# schematic.net
KiCad netlist of a schematic drawn in EAGLE
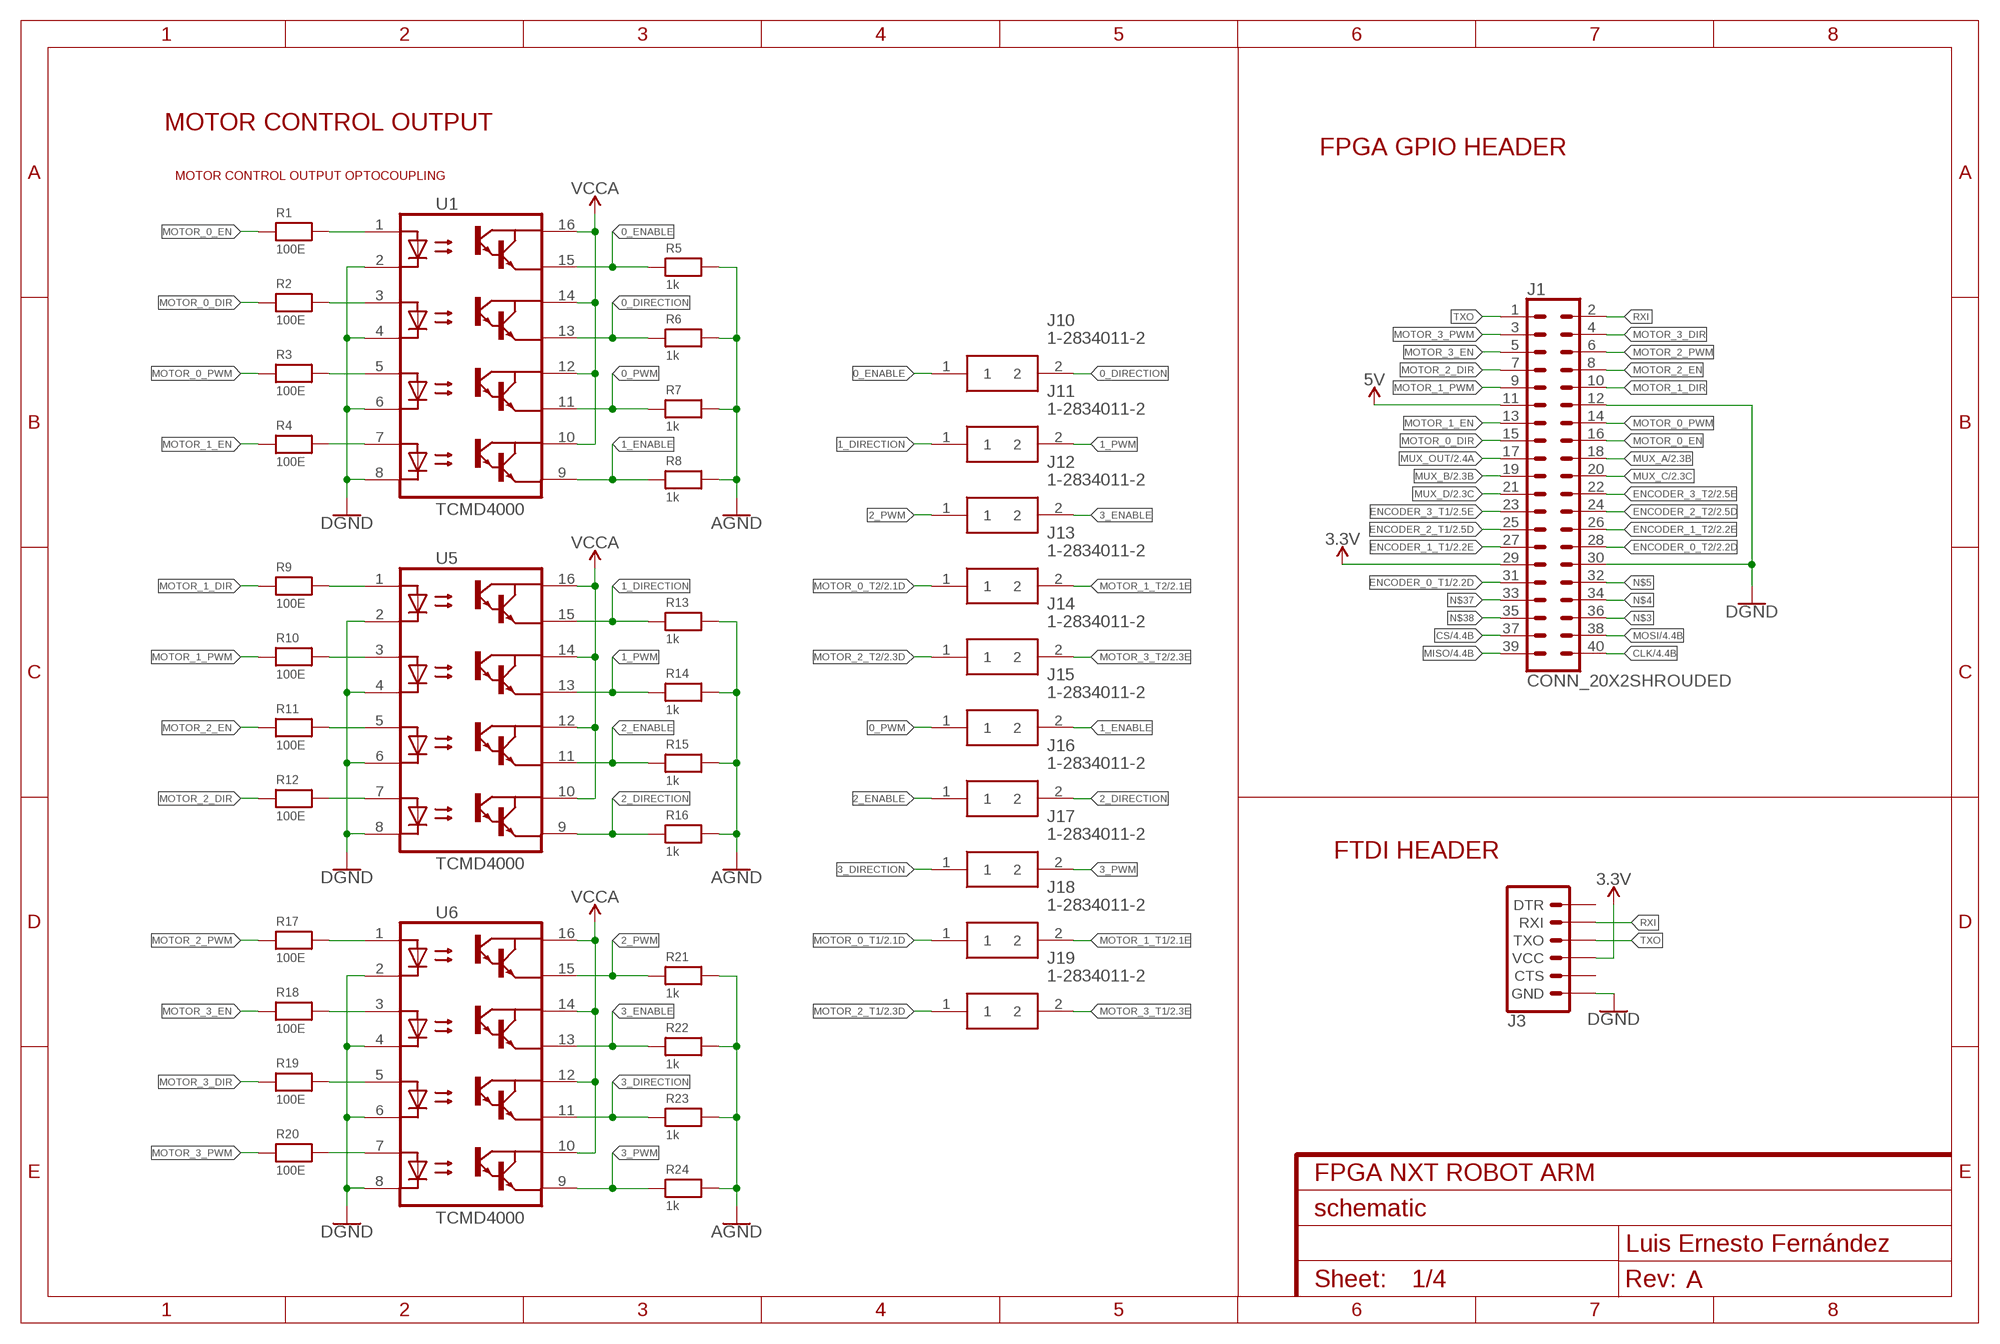
[diagram p0: schematic, sheet 1]
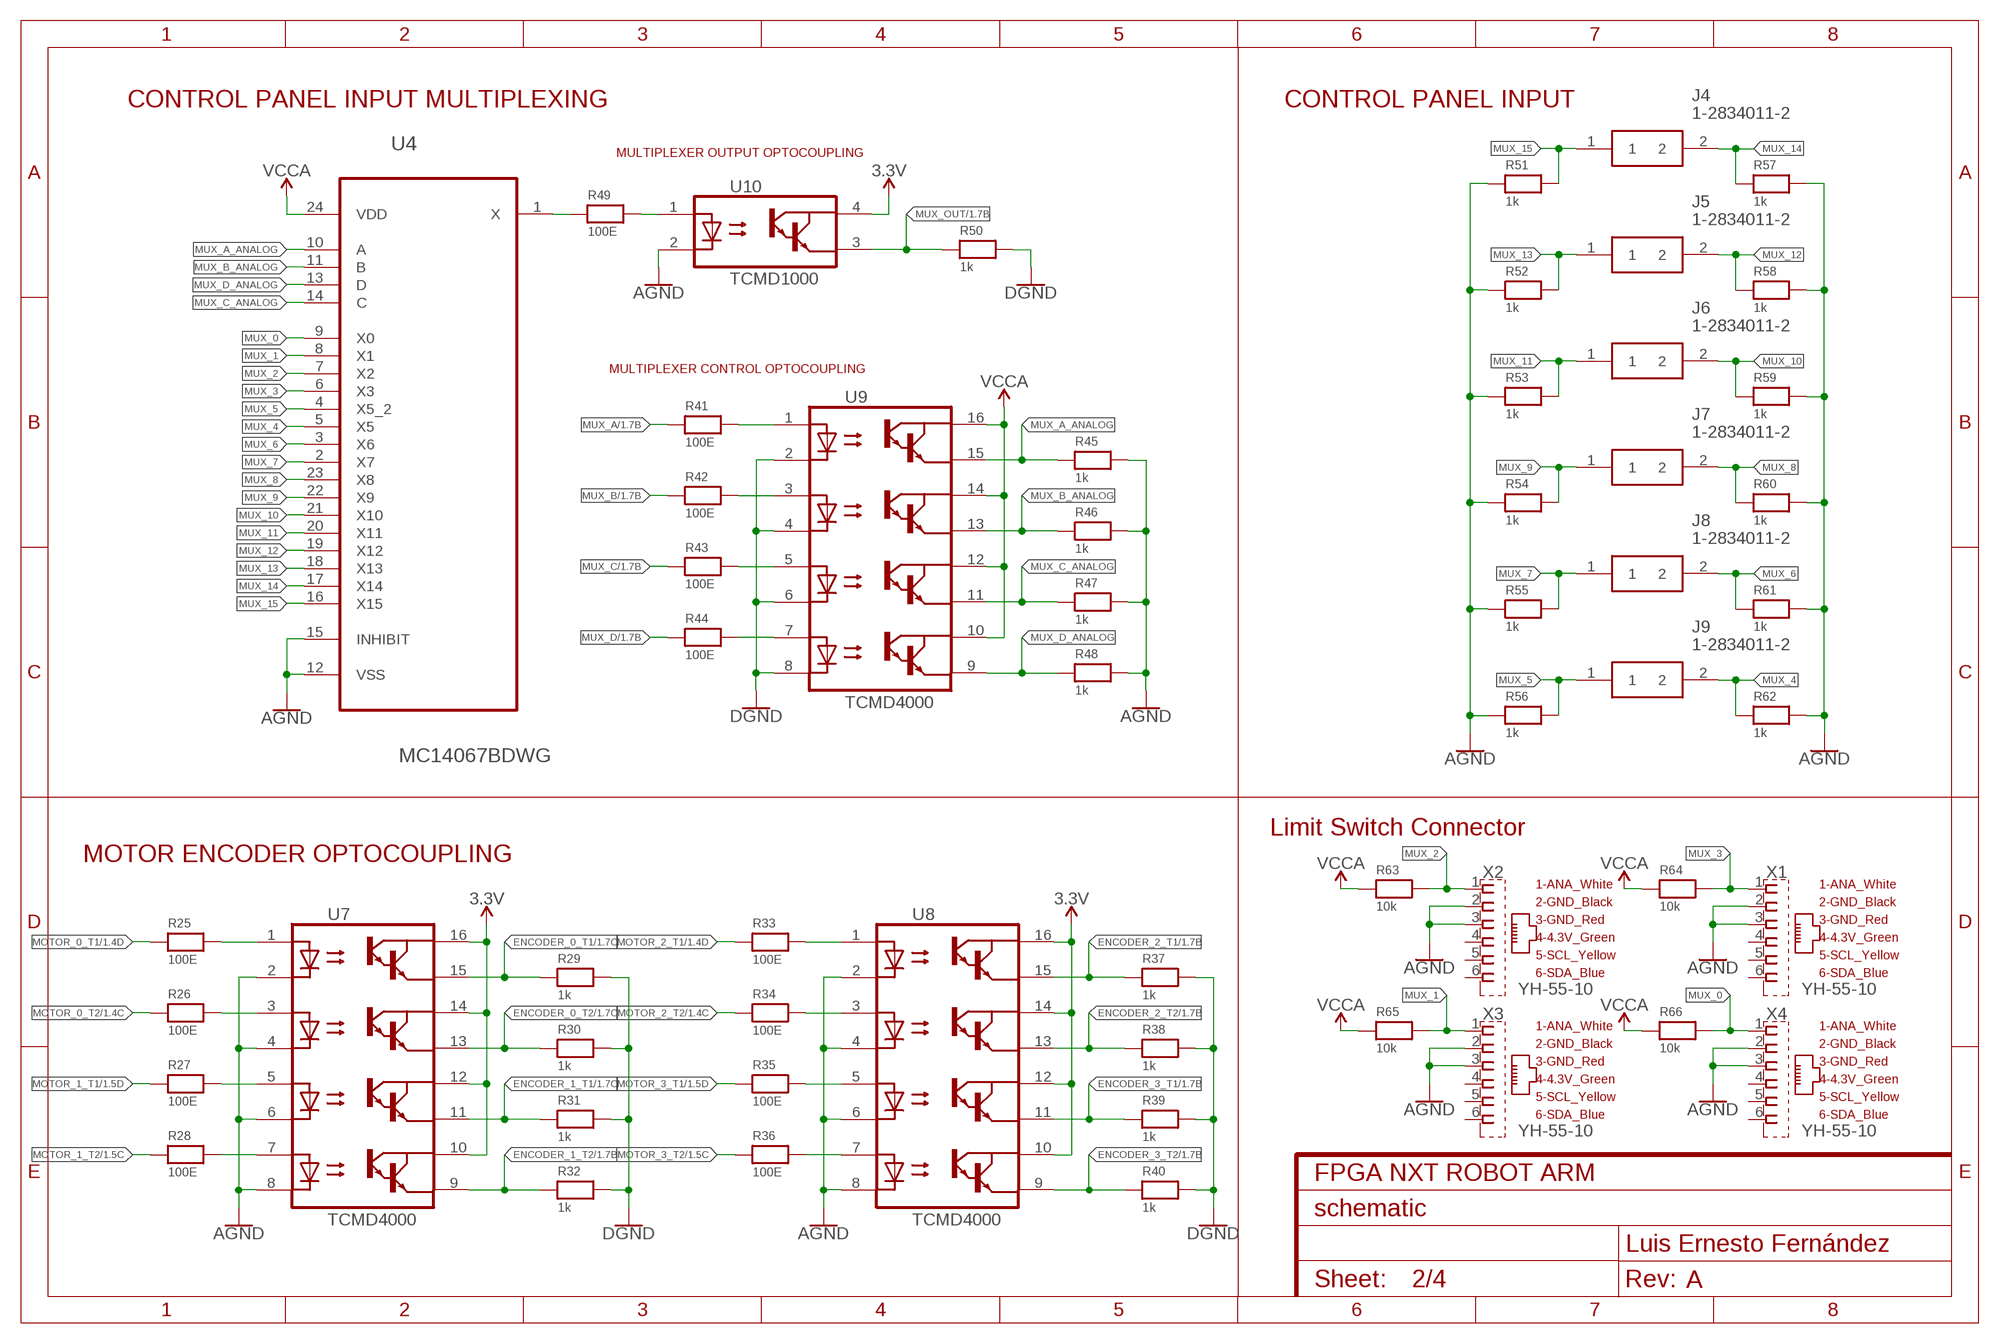
[diagram p1: schematic, sheet 2]
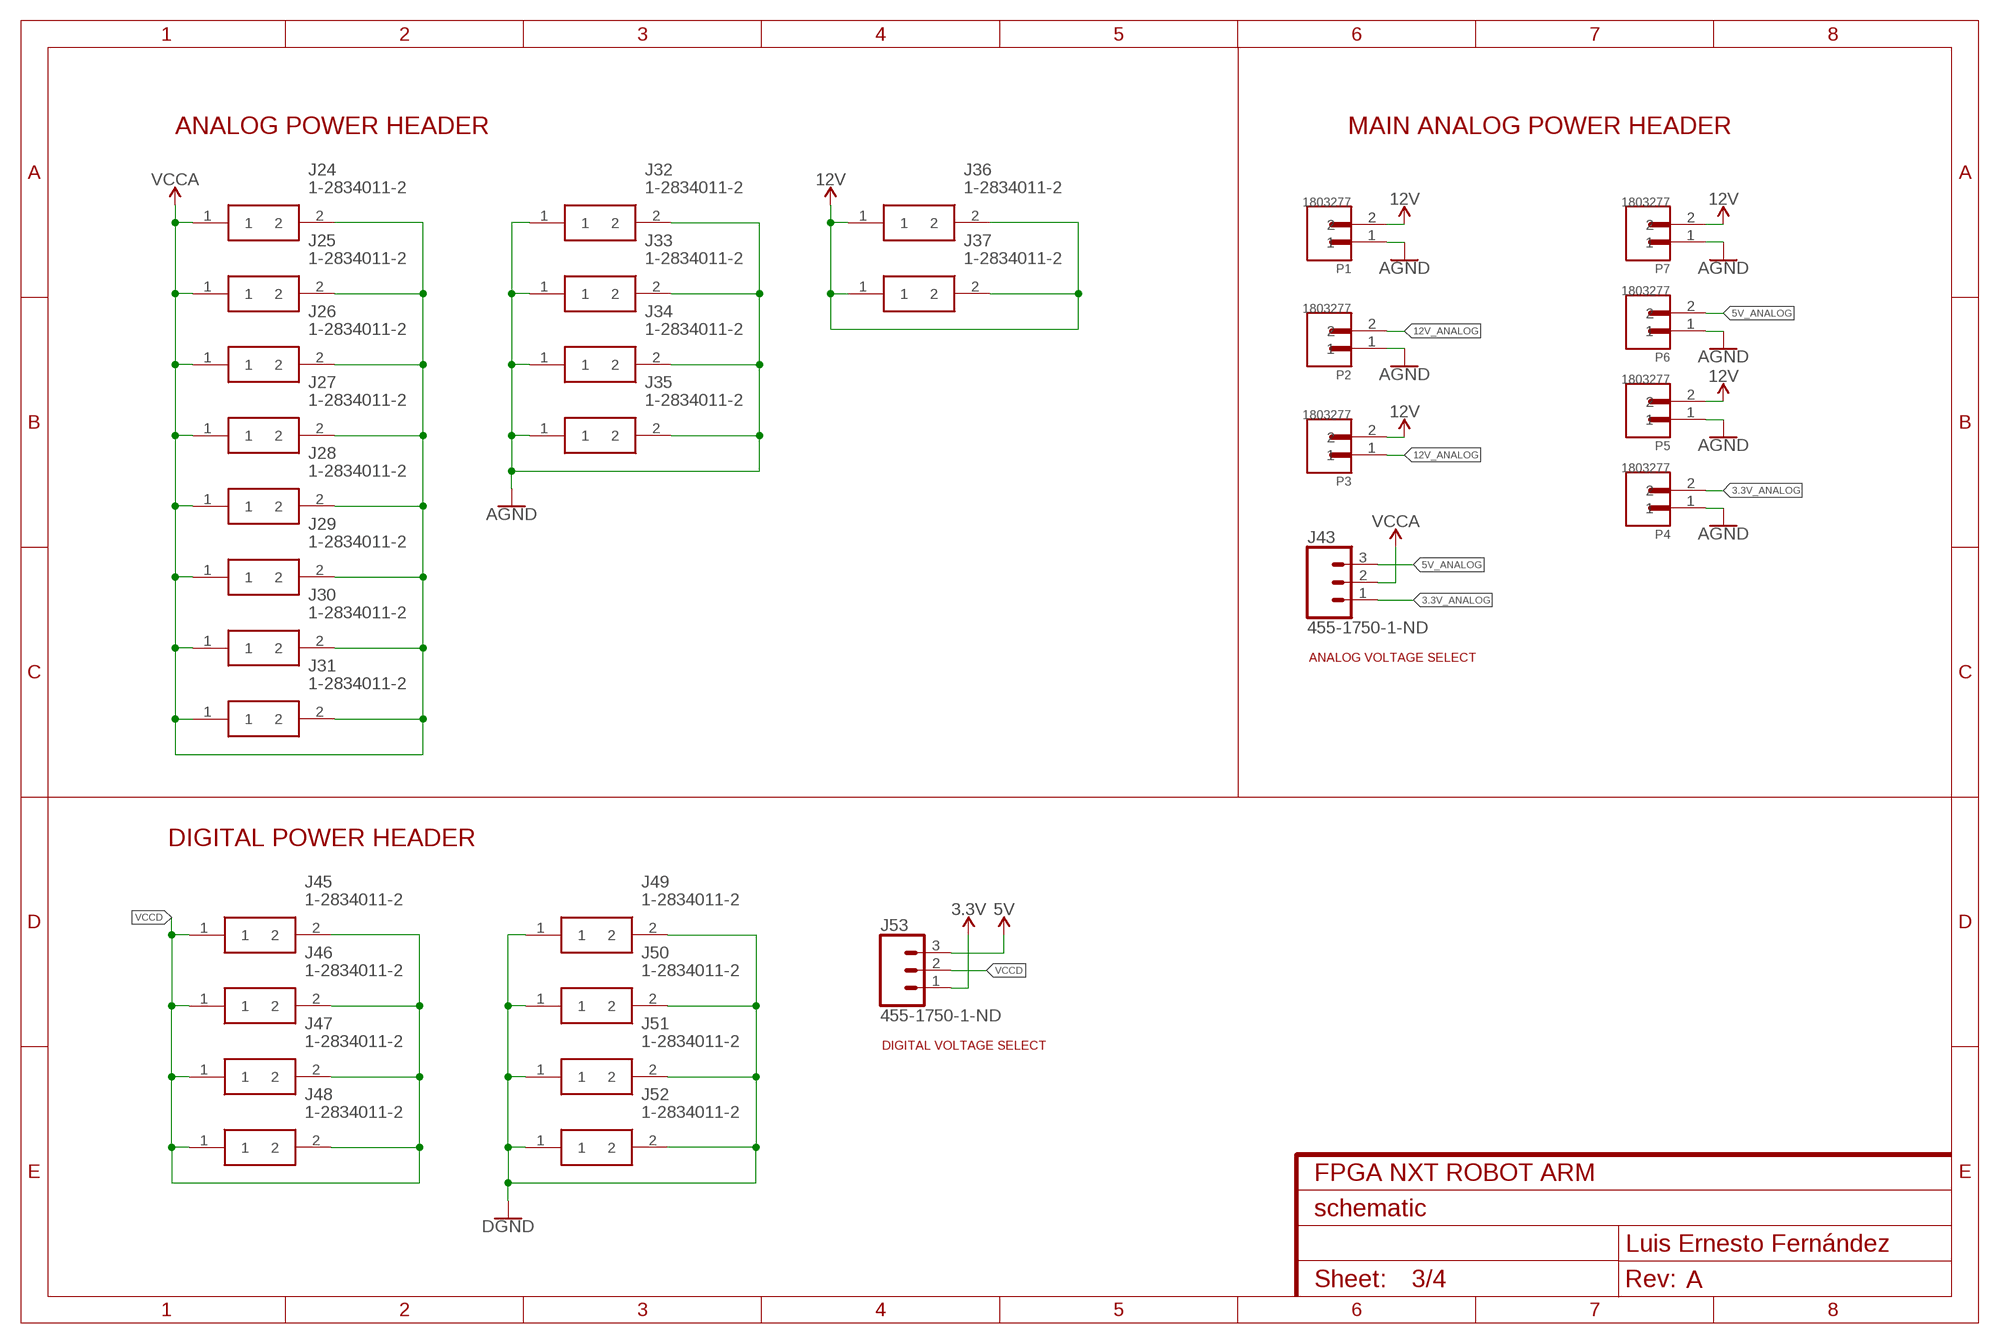
[diagram p2: schematic, sheet 3]
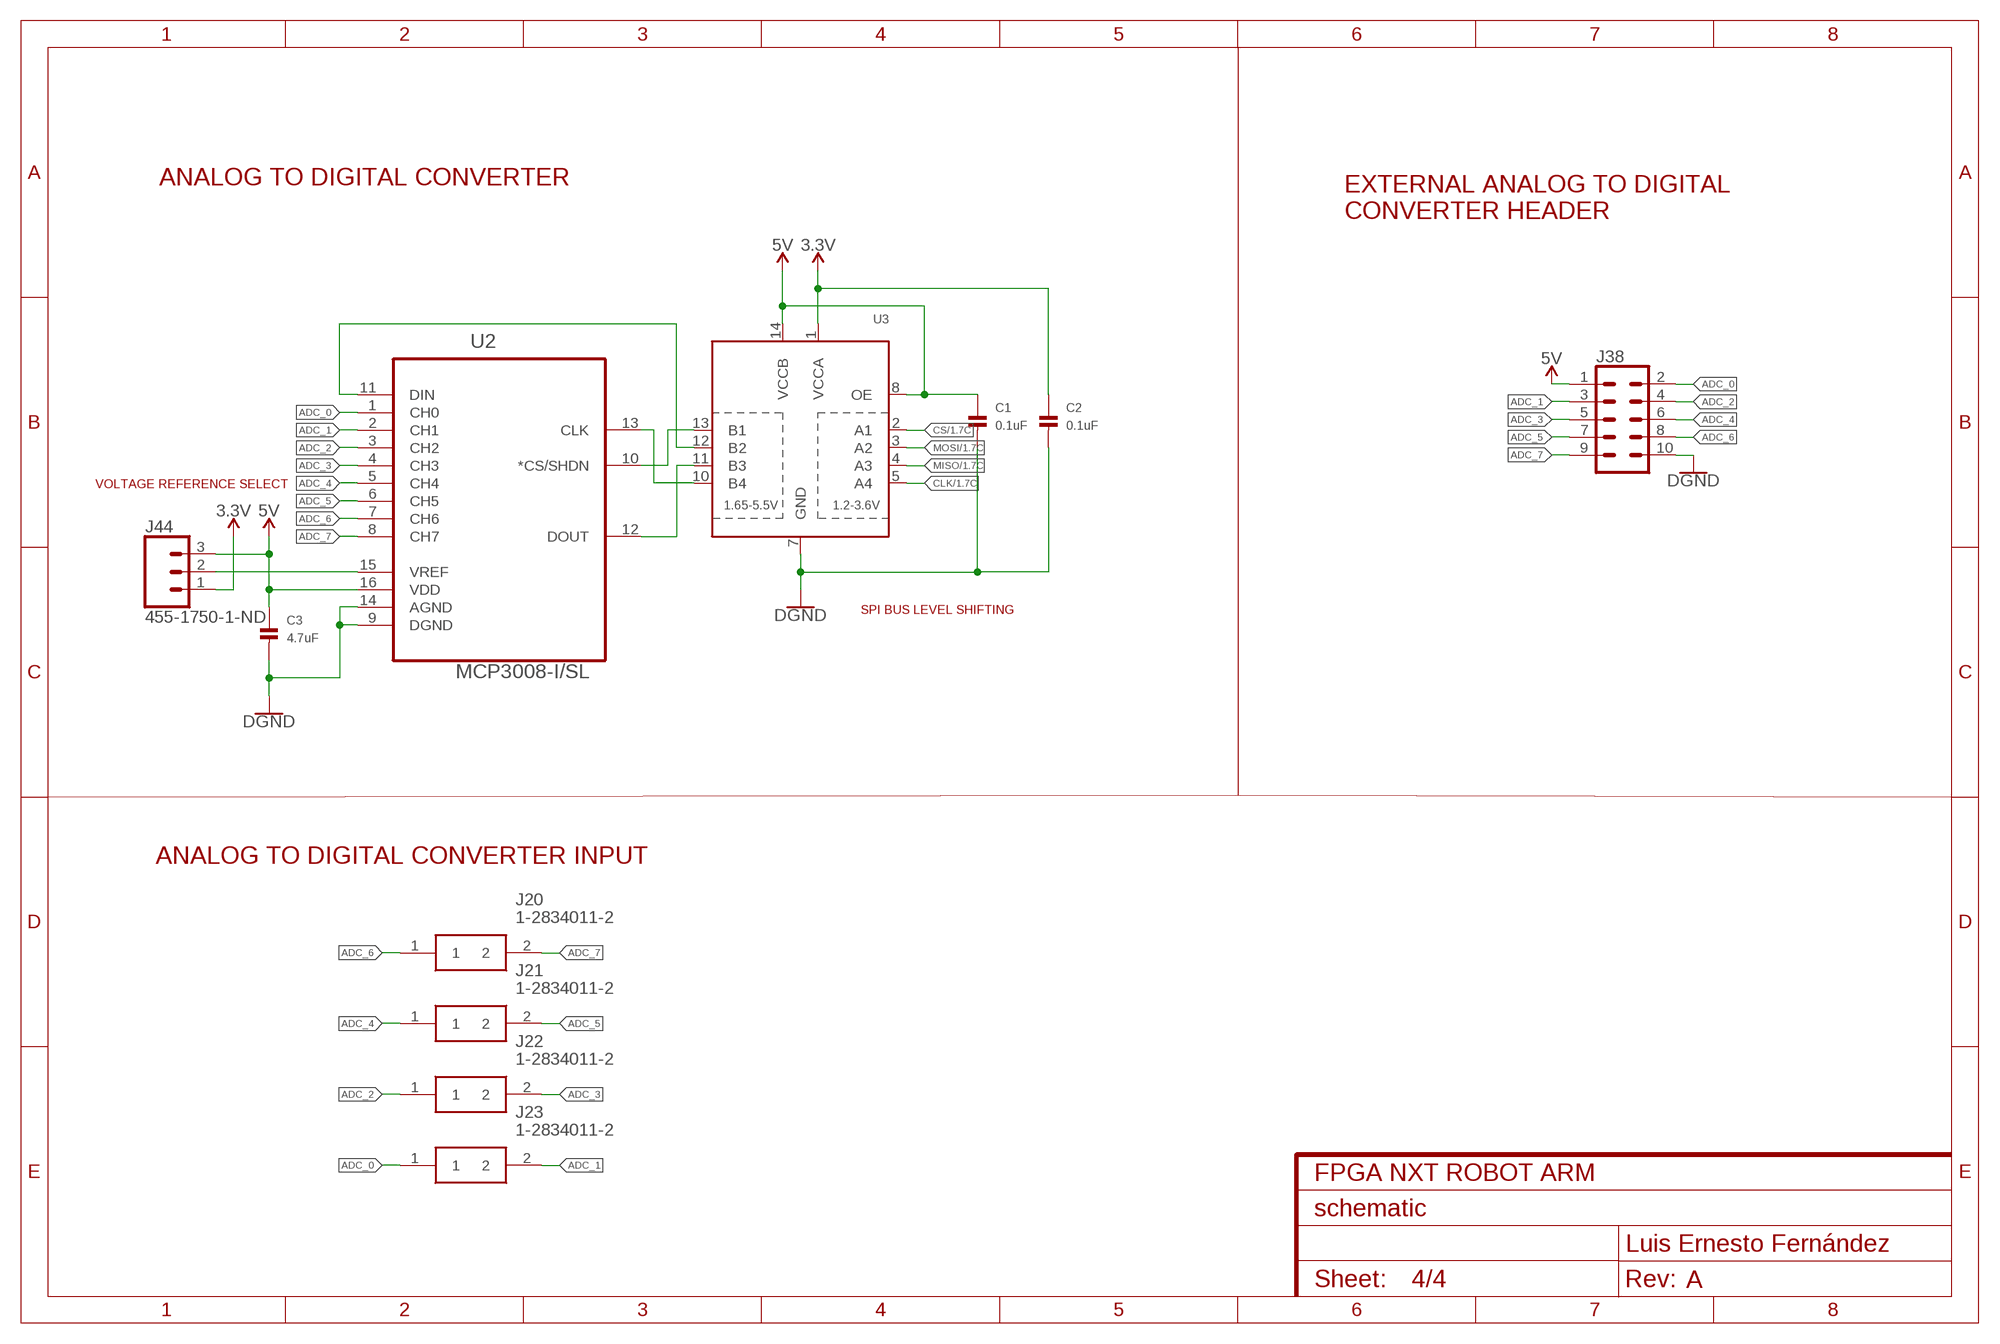
[diagram p3: schematic, sheet 4]

(export (version "E")
  (design (tool "Eeschema 10.0.6"))
  (components
    (comp (ref "C1")
      (value "0.1uF")
      (footprint "eagle-import:0805_NOTHERMALS")
      (libsource (lib "eagle-import") (part "CAP_CERAMIC0805-NOTHERMALS"))
    )
    (comp (ref "C2")
      (value "0.1uF")
      (footprint "eagle-import:0805_NOTHERMALS")
      (libsource (lib "eagle-import") (part "CAP_CERAMIC0805-NOTHERMALS"))
    )
    (comp (ref "C3")
      (value "4.7uF")
      (footprint "eagle-import:0805_NOTHERMALS")
      (libsource (lib "eagle-import") (part "CAP_CERAMIC0805-NOTHERMALS"))
    )
    (comp (ref "J20")
      (value "1-2834011-2")
      (footprint "eagle-import:128340112")
      (fields (field (name "RS_PART_NUMBER") "1649131"))
      (libsource (lib "eagle-import") (part "1-2834011-2"))
    )
    (comp (ref "J21")
      (value "1-2834011-2")
      (footprint "eagle-import:128340112")
      (fields (field (name "RS_PART_NUMBER") "1649131"))
      (libsource (lib "eagle-import") (part "1-2834011-2"))
    )
    (comp (ref "J22")
      (value "1-2834011-2")
      (footprint "eagle-import:128340112")
      (fields (field (name "RS_PART_NUMBER") "1649131"))
      (libsource (lib "eagle-import") (part "1-2834011-2"))
    )
    (comp (ref "J23")
      (value "1-2834011-2")
      (footprint "eagle-import:128340112")
      (fields (field (name "RS_PART_NUMBER") "1649131"))
      (libsource (lib "eagle-import") (part "1-2834011-2"))
    )
    (comp (ref "J38")
      (value "CONN_05X2SHD")
      (footprint "eagle-import:2X5-SHROUDED")
      (libsource (lib "eagle-import") (part "CONN_05X2SHD"))
    )
    (comp (ref "J44")
      (value "455-1750-1-ND")
      (footprint "eagle-import:1X03")
      (libsource (lib "eagle-import") (part "CONN_03"))
    )
    (comp (ref "U2")
      (value "MCP3008-I/SL")
      (footprint "eagle-import:SOIC127P600X175-16N")
      (fields (field (name "MF") "Microchip"))
      (libsource (lib "eagle-import") (part "MCP3008-I/SL"))
    )
    (comp (ref "U3")
      (value "TXB0104PWR")
      (footprint "eagle-import:TSSOP14")
      (libsource (lib "eagle-import") (part "TXB0104PWR"))
    )
    (comp (ref "J1")
      (value "CONN_20X2SHROUDED")
      (footprint "eagle-import:2X20_SHROUDED")
      (libsource (lib "eagle-import") (part "CONN_20X2SHROUDED"))
    )
    (comp (ref "J3")
      (value "6_PIN_SERIAL_TARGET")
      (footprint "eagle-import:1X06")
      (libsource (lib "eagle-import") (part "6_PIN_SERIAL_TARGET"))
    )
    (comp (ref "J10")
      (value "1-2834011-2")
      (footprint "eagle-import:128340112")
      (fields (field (name "RS_PART_NUMBER") "1649131"))
      (libsource (lib "eagle-import") (part "1-2834011-2"))
    )
    (comp (ref "J11")
      (value "1-2834011-2")
      (footprint "eagle-import:128340112")
      (fields (field (name "RS_PART_NUMBER") "1649131"))
      (libsource (lib "eagle-import") (part "1-2834011-2"))
    )
    (comp (ref "J12")
      (value "1-2834011-2")
      (footprint "eagle-import:128340112")
      (fields (field (name "RS_PART_NUMBER") "1649131"))
      (libsource (lib "eagle-import") (part "1-2834011-2"))
    )
    (comp (ref "J13")
      (value "1-2834011-2")
      (footprint "eagle-import:128340112")
      (fields (field (name "RS_PART_NUMBER") "1649131"))
      (libsource (lib "eagle-import") (part "1-2834011-2"))
    )
    (comp (ref "J14")
      (value "1-2834011-2")
      (footprint "eagle-import:128340112")
      (fields (field (name "RS_PART_NUMBER") "1649131"))
      (libsource (lib "eagle-import") (part "1-2834011-2"))
    )
    (comp (ref "J15")
      (value "1-2834011-2")
      (footprint "eagle-import:128340112")
      (fields (field (name "RS_PART_NUMBER") "1649131"))
      (libsource (lib "eagle-import") (part "1-2834011-2"))
    )
    (comp (ref "J16")
      (value "1-2834011-2")
      (footprint "eagle-import:128340112")
      (fields (field (name "RS_PART_NUMBER") "1649131"))
      (libsource (lib "eagle-import") (part "1-2834011-2"))
    )
    (comp (ref "J17")
      (value "1-2834011-2")
      (footprint "eagle-import:128340112")
      (fields (field (name "RS_PART_NUMBER") "1649131"))
      (libsource (lib "eagle-import") (part "1-2834011-2"))
    )
    (comp (ref "J18")
      (value "1-2834011-2")
      (footprint "eagle-import:128340112")
      (fields (field (name "RS_PART_NUMBER") "1649131"))
      (libsource (lib "eagle-import") (part "1-2834011-2"))
    )
    (comp (ref "J19")
      (value "1-2834011-2")
      (footprint "eagle-import:128340112")
      (fields (field (name "RS_PART_NUMBER") "1649131"))
      (libsource (lib "eagle-import") (part "1-2834011-2"))
    )
    (comp (ref "R1")
      (value "100E")
      (footprint "eagle-import:0805_NOTHERMALS")
      (libsource (lib "eagle-import") (part "RESISTOR0805_NOTHERMALS"))
    )
    (comp (ref "R2")
      (value "100E")
      (footprint "eagle-import:0805_NOTHERMALS")
      (libsource (lib "eagle-import") (part "RESISTOR0805_NOTHERMALS"))
    )
    (comp (ref "R3")
      (value "100E")
      (footprint "eagle-import:0805_NOTHERMALS")
      (libsource (lib "eagle-import") (part "RESISTOR0805_NOTHERMALS"))
    )
    (comp (ref "R4")
      (value "100E")
      (footprint "eagle-import:0805_NOTHERMALS")
      (libsource (lib "eagle-import") (part "RESISTOR0805_NOTHERMALS"))
    )
    (comp (ref "R5")
      (value "1k")
      (footprint "eagle-import:0805_NOTHERMALS")
      (libsource (lib "eagle-import") (part "RESISTOR0805_NOTHERMALS"))
    )
    (comp (ref "R6")
      (value "1k")
      (footprint "eagle-import:0805_NOTHERMALS")
      (libsource (lib "eagle-import") (part "RESISTOR0805_NOTHERMALS"))
    )
    (comp (ref "R7")
      (value "1k")
      (footprint "eagle-import:0805_NOTHERMALS")
      (libsource (lib "eagle-import") (part "RESISTOR0805_NOTHERMALS"))
    )
    (comp (ref "R8")
      (value "1k")
      (footprint "eagle-import:0805_NOTHERMALS")
      (libsource (lib "eagle-import") (part "RESISTOR0805_NOTHERMALS"))
    )
    (comp (ref "R9")
      (value "100E")
      (footprint "eagle-import:0805_NOTHERMALS")
      (libsource (lib "eagle-import") (part "RESISTOR0805_NOTHERMALS"))
    )
    (comp (ref "R10")
      (value "100E")
      (footprint "eagle-import:0805_NOTHERMALS")
      (libsource (lib "eagle-import") (part "RESISTOR0805_NOTHERMALS"))
    )
    (comp (ref "R11")
      (value "100E")
      (footprint "eagle-import:0805_NOTHERMALS")
      (libsource (lib "eagle-import") (part "RESISTOR0805_NOTHERMALS"))
    )
    (comp (ref "R12")
      (value "100E")
      (footprint "eagle-import:0805_NOTHERMALS")
      (libsource (lib "eagle-import") (part "RESISTOR0805_NOTHERMALS"))
    )
    (comp (ref "R13")
      (value "1k")
      (footprint "eagle-import:0805_NOTHERMALS")
      (libsource (lib "eagle-import") (part "RESISTOR0805_NOTHERMALS"))
    )
    (comp (ref "R14")
      (value "1k")
      (footprint "eagle-import:0805_NOTHERMALS")
      (libsource (lib "eagle-import") (part "RESISTOR0805_NOTHERMALS"))
    )
    (comp (ref "R15")
      (value "1k")
      (footprint "eagle-import:0805_NOTHERMALS")
      (libsource (lib "eagle-import") (part "RESISTOR0805_NOTHERMALS"))
    )
    (comp (ref "R16")
      (value "1k")
      (footprint "eagle-import:0805_NOTHERMALS")
      (libsource (lib "eagle-import") (part "RESISTOR0805_NOTHERMALS"))
    )
    (comp (ref "R17")
      (value "100E")
      (footprint "eagle-import:0805_NOTHERMALS")
      (libsource (lib "eagle-import") (part "RESISTOR0805_NOTHERMALS"))
    )
    (comp (ref "R18")
      (value "100E")
      (footprint "eagle-import:0805_NOTHERMALS")
      (libsource (lib "eagle-import") (part "RESISTOR0805_NOTHERMALS"))
    )
    (comp (ref "R19")
      (value "100E")
      (footprint "eagle-import:0805_NOTHERMALS")
      (libsource (lib "eagle-import") (part "RESISTOR0805_NOTHERMALS"))
    )
    (comp (ref "R20")
      (value "100E")
      (footprint "eagle-import:0805_NOTHERMALS")
      (libsource (lib "eagle-import") (part "RESISTOR0805_NOTHERMALS"))
    )
    (comp (ref "R21")
      (value "1k")
      (footprint "eagle-import:0805_NOTHERMALS")
      (libsource (lib "eagle-import") (part "RESISTOR0805_NOTHERMALS"))
    )
    (comp (ref "R22")
      (value "1k")
      (footprint "eagle-import:0805_NOTHERMALS")
      (libsource (lib "eagle-import") (part "RESISTOR0805_NOTHERMALS"))
    )
    (comp (ref "R23")
      (value "1k")
      (footprint "eagle-import:0805_NOTHERMALS")
      (libsource (lib "eagle-import") (part "RESISTOR0805_NOTHERMALS"))
    )
    (comp (ref "R24")
      (value "1k")
      (footprint "eagle-import:0805_NOTHERMALS")
      (libsource (lib "eagle-import") (part "RESISTOR0805_NOTHERMALS"))
    )
    (comp (ref "U1")
      (value "TCMD4000")
      (footprint "eagle-import:SOIC127P686X201-16N")
      (fields (field (name "MF") "Vishay Semiconductor"))
      (libsource (lib "eagle-import") (part "TCMD4000"))
    )
    (comp (ref "U5")
      (value "TCMD4000")
      (footprint "eagle-import:SOIC127P686X201-16N")
      (fields (field (name "MF") "Vishay Semiconductor"))
      (libsource (lib "eagle-import") (part "TCMD4000"))
    )
    (comp (ref "U6")
      (value "TCMD4000")
      (footprint "eagle-import:SOIC127P686X201-16N")
      (fields (field (name "MF") "Vishay Semiconductor"))
      (libsource (lib "eagle-import") (part "TCMD4000"))
    )
    (comp (ref "J4")
      (value "1-2834011-2")
      (footprint "eagle-import:128340112")
      (fields (field (name "RS_PART_NUMBER") "1649131"))
      (libsource (lib "eagle-import") (part "1-2834011-2"))
    )
    (comp (ref "J5")
      (value "1-2834011-2")
      (footprint "eagle-import:128340112")
      (fields (field (name "RS_PART_NUMBER") "1649131"))
      (libsource (lib "eagle-import") (part "1-2834011-2"))
    )
    (comp (ref "J6")
      (value "1-2834011-2")
      (footprint "eagle-import:128340112")
      (fields (field (name "RS_PART_NUMBER") "1649131"))
      (libsource (lib "eagle-import") (part "1-2834011-2"))
    )
    (comp (ref "J7")
      (value "1-2834011-2")
      (footprint "eagle-import:128340112")
      (fields (field (name "RS_PART_NUMBER") "1649131"))
      (libsource (lib "eagle-import") (part "1-2834011-2"))
    )
    (comp (ref "J8")
      (value "1-2834011-2")
      (footprint "eagle-import:128340112")
      (fields (field (name "RS_PART_NUMBER") "1649131"))
      (libsource (lib "eagle-import") (part "1-2834011-2"))
    )
    (comp (ref "J9")
      (value "1-2834011-2")
      (footprint "eagle-import:128340112")
      (fields (field (name "RS_PART_NUMBER") "1649131"))
      (libsource (lib "eagle-import") (part "1-2834011-2"))
    )
    (comp (ref "R25")
      (value "100E")
      (footprint "eagle-import:0805_NOTHERMALS")
      (libsource (lib "eagle-import") (part "RESISTOR0805_NOTHERMALS"))
    )
    (comp (ref "R26")
      (value "100E")
      (footprint "eagle-import:0805_NOTHERMALS")
      (libsource (lib "eagle-import") (part "RESISTOR0805_NOTHERMALS"))
    )
    (comp (ref "R27")
      (value "100E")
      (footprint "eagle-import:0805_NOTHERMALS")
      (libsource (lib "eagle-import") (part "RESISTOR0805_NOTHERMALS"))
    )
    (comp (ref "R28")
      (value "100E")
      (footprint "eagle-import:0805_NOTHERMALS")
      (libsource (lib "eagle-import") (part "RESISTOR0805_NOTHERMALS"))
    )
    (comp (ref "R29")
      (value "1k")
      (footprint "eagle-import:0805_NOTHERMALS")
      (libsource (lib "eagle-import") (part "RESISTOR0805_NOTHERMALS"))
    )
    (comp (ref "R30")
      (value "1k")
      (footprint "eagle-import:0805_NOTHERMALS")
      (libsource (lib "eagle-import") (part "RESISTOR0805_NOTHERMALS"))
    )
    (comp (ref "R31")
      (value "1k")
      (footprint "eagle-import:0805_NOTHERMALS")
      (libsource (lib "eagle-import") (part "RESISTOR0805_NOTHERMALS"))
    )
    (comp (ref "R32")
      (value "1k")
      (footprint "eagle-import:0805_NOTHERMALS")
      (libsource (lib "eagle-import") (part "RESISTOR0805_NOTHERMALS"))
    )
    (comp (ref "R33")
      (value "100E")
      (footprint "eagle-import:0805_NOTHERMALS")
      (libsource (lib "eagle-import") (part "RESISTOR0805_NOTHERMALS"))
    )
    (comp (ref "R34")
      (value "100E")
      (footprint "eagle-import:0805_NOTHERMALS")
      (libsource (lib "eagle-import") (part "RESISTOR0805_NOTHERMALS"))
    )
    (comp (ref "R35")
      (value "100E")
      (footprint "eagle-import:0805_NOTHERMALS")
      (libsource (lib "eagle-import") (part "RESISTOR0805_NOTHERMALS"))
    )
    (comp (ref "R36")
      (value "100E")
      (footprint "eagle-import:0805_NOTHERMALS")
      (libsource (lib "eagle-import") (part "RESISTOR0805_NOTHERMALS"))
    )
    (comp (ref "R37")
      (value "1k")
      (footprint "eagle-import:0805_NOTHERMALS")
      (libsource (lib "eagle-import") (part "RESISTOR0805_NOTHERMALS"))
    )
    (comp (ref "R38")
      (value "1k")
      (footprint "eagle-import:0805_NOTHERMALS")
      (libsource (lib "eagle-import") (part "RESISTOR0805_NOTHERMALS"))
    )
    (comp (ref "R39")
      (value "1k")
      (footprint "eagle-import:0805_NOTHERMALS")
      (libsource (lib "eagle-import") (part "RESISTOR0805_NOTHERMALS"))
    )
    (comp (ref "R40")
      (value "1k")
      (footprint "eagle-import:0805_NOTHERMALS")
      (libsource (lib "eagle-import") (part "RESISTOR0805_NOTHERMALS"))
    )
    (comp (ref "R41")
      (value "100E")
      (footprint "eagle-import:0805_NOTHERMALS")
      (libsource (lib "eagle-import") (part "RESISTOR0805_NOTHERMALS"))
    )
    (comp (ref "R42")
      (value "100E")
      (footprint "eagle-import:0805_NOTHERMALS")
      (libsource (lib "eagle-import") (part "RESISTOR0805_NOTHERMALS"))
    )
    (comp (ref "R43")
      (value "100E")
      (footprint "eagle-import:0805_NOTHERMALS")
      (libsource (lib "eagle-import") (part "RESISTOR0805_NOTHERMALS"))
    )
    (comp (ref "R44")
      (value "100E")
      (footprint "eagle-import:0805_NOTHERMALS")
      (libsource (lib "eagle-import") (part "RESISTOR0805_NOTHERMALS"))
    )
    (comp (ref "R45")
      (value "1k")
      (footprint "eagle-import:0805_NOTHERMALS")
      (libsource (lib "eagle-import") (part "RESISTOR0805_NOTHERMALS"))
    )
    (comp (ref "R46")
      (value "1k")
      (footprint "eagle-import:0805_NOTHERMALS")
      (libsource (lib "eagle-import") (part "RESISTOR0805_NOTHERMALS"))
    )
    (comp (ref "R47")
      (value "1k")
      (footprint "eagle-import:0805_NOTHERMALS")
      (libsource (lib "eagle-import") (part "RESISTOR0805_NOTHERMALS"))
    )
    (comp (ref "R48")
      (value "1k")
      (footprint "eagle-import:0805_NOTHERMALS")
      (libsource (lib "eagle-import") (part "RESISTOR0805_NOTHERMALS"))
    )
    (comp (ref "R49")
      (value "100E")
      (footprint "eagle-import:0805_NOTHERMALS")
      (libsource (lib "eagle-import") (part "RESISTOR0805_NOTHERMALS"))
    )
    (comp (ref "R50")
      (value "1k")
      (footprint "eagle-import:0805_NOTHERMALS")
      (libsource (lib "eagle-import") (part "RESISTOR0805_NOTHERMALS"))
    )
    (comp (ref "R51")
      (value "1k")
      (footprint "eagle-import:0805_NOTHERMALS")
      (libsource (lib "eagle-import") (part "RESISTOR0805_NOTHERMALS"))
    )
    (comp (ref "R52")
      (value "1k")
      (footprint "eagle-import:0805_NOTHERMALS")
      (libsource (lib "eagle-import") (part "RESISTOR0805_NOTHERMALS"))
    )
    (comp (ref "R53")
      (value "1k")
      (footprint "eagle-import:0805_NOTHERMALS")
      (libsource (lib "eagle-import") (part "RESISTOR0805_NOTHERMALS"))
    )
    (comp (ref "R54")
      (value "1k")
      (footprint "eagle-import:0805_NOTHERMALS")
      (libsource (lib "eagle-import") (part "RESISTOR0805_NOTHERMALS"))
    )
    (comp (ref "R55")
      (value "1k")
      (footprint "eagle-import:0805_NOTHERMALS")
      (libsource (lib "eagle-import") (part "RESISTOR0805_NOTHERMALS"))
    )
    (comp (ref "R56")
      (value "1k")
      (footprint "eagle-import:0805_NOTHERMALS")
      (libsource (lib "eagle-import") (part "RESISTOR0805_NOTHERMALS"))
    )
    (comp (ref "R57")
      (value "1k")
      (footprint "eagle-import:0805_NOTHERMALS")
      (libsource (lib "eagle-import") (part "RESISTOR0805_NOTHERMALS"))
    )
    (comp (ref "R58")
      (value "1k")
      (footprint "eagle-import:0805_NOTHERMALS")
      (libsource (lib "eagle-import") (part "RESISTOR0805_NOTHERMALS"))
    )
    (comp (ref "R59")
      (value "1k")
      (footprint "eagle-import:0805_NOTHERMALS")
      (libsource (lib "eagle-import") (part "RESISTOR0805_NOTHERMALS"))
    )
    (comp (ref "R60")
      (value "1k")
      (footprint "eagle-import:0805_NOTHERMALS")
      (libsource (lib "eagle-import") (part "RESISTOR0805_NOTHERMALS"))
    )
    (comp (ref "R61")
      (value "1k")
      (footprint "eagle-import:0805_NOTHERMALS")
      (libsource (lib "eagle-import") (part "RESISTOR0805_NOTHERMALS"))
    )
    (comp (ref "R62")
      (value "1k")
      (footprint "eagle-import:0805_NOTHERMALS")
      (libsource (lib "eagle-import") (part "RESISTOR0805_NOTHERMALS"))
    )
    (comp (ref "R63")
      (value "10k")
      (footprint "eagle-import:0805_NOTHERMALS")
      (libsource (lib "eagle-import") (part "RESISTOR0805_NOTHERMALS"))
    )
    (comp (ref "R64")
      (value "10k")
      (footprint "eagle-import:0805_NOTHERMALS")
      (libsource (lib "eagle-import") (part "RESISTOR0805_NOTHERMALS"))
    )
    (comp (ref "R65")
      (value "10k")
      (footprint "eagle-import:0805_NOTHERMALS")
      (libsource (lib "eagle-import") (part "RESISTOR0805_NOTHERMALS"))
    )
    (comp (ref "R66")
      (value "10k")
      (footprint "eagle-import:0805_NOTHERMALS")
      (libsource (lib "eagle-import") (part "RESISTOR0805_NOTHERMALS"))
    )
    (comp (ref "U4")
      (value "MC14067BDWG")
      (footprint "eagle-import:SOIC127P1030X265-24N")
      (libsource (lib "eagle-import") (part "MC14067BDWG"))
    )
    (comp (ref "U7")
      (value "TCMD4000")
      (footprint "eagle-import:SOIC127P686X201-16N")
      (fields (field (name "MF") "Vishay Semiconductor"))
      (libsource (lib "eagle-import") (part "TCMD4000"))
    )
    (comp (ref "U8")
      (value "TCMD4000")
      (footprint "eagle-import:SOIC127P686X201-16N")
      (fields (field (name "MF") "Vishay Semiconductor"))
      (libsource (lib "eagle-import") (part "TCMD4000"))
    )
    (comp (ref "U9")
      (value "TCMD4000")
      (footprint "eagle-import:SOIC127P686X201-16N")
      (fields (field (name "MF") "Vishay Semiconductor"))
      (libsource (lib "eagle-import") (part "TCMD4000"))
    )
    (comp (ref "U10")
      (value "TCMD1000")
      (footprint "eagle-import:SOIC254P695X210-4N")
      (fields (field (name "MF") "Vishay"))
      (libsource (lib "eagle-import") (part "TCMD1000"))
    )
    (comp (ref "X1")
      (value "YH-55-10")
      (footprint "eagle-import:YH-55-10")
      (libsource (lib "eagle-import") (part "YH-55-10"))
    )
    (comp (ref "X2")
      (value "YH-55-10")
      (footprint "eagle-import:YH-55-10")
      (libsource (lib "eagle-import") (part "YH-55-10"))
    )
    (comp (ref "X3")
      (value "YH-55-10")
      (footprint "eagle-import:YH-55-10")
      (libsource (lib "eagle-import") (part "YH-55-10"))
    )
    (comp (ref "X4")
      (value "YH-55-10")
      (footprint "eagle-import:YH-55-10")
      (libsource (lib "eagle-import") (part "YH-55-10"))
    )
    (comp (ref "J24")
      (value "1-2834011-2")
      (footprint "eagle-import:128340112")
      (fields (field (name "RS_PART_NUMBER") "1649131"))
      (libsource (lib "eagle-import") (part "1-2834011-2"))
    )
    (comp (ref "J25")
      (value "1-2834011-2")
      (footprint "eagle-import:128340112")
      (fields (field (name "RS_PART_NUMBER") "1649131"))
      (libsource (lib "eagle-import") (part "1-2834011-2"))
    )
    (comp (ref "J26")
      (value "1-2834011-2")
      (footprint "eagle-import:128340112")
      (fields (field (name "RS_PART_NUMBER") "1649131"))
      (libsource (lib "eagle-import") (part "1-2834011-2"))
    )
    (comp (ref "J27")
      (value "1-2834011-2")
      (footprint "eagle-import:128340112")
      (fields (field (name "RS_PART_NUMBER") "1649131"))
      (libsource (lib "eagle-import") (part "1-2834011-2"))
    )
    (comp (ref "J28")
      (value "1-2834011-2")
      (footprint "eagle-import:128340112")
      (fields (field (name "RS_PART_NUMBER") "1649131"))
      (libsource (lib "eagle-import") (part "1-2834011-2"))
    )
    (comp (ref "J29")
      (value "1-2834011-2")
      (footprint "eagle-import:128340112")
      (fields (field (name "RS_PART_NUMBER") "1649131"))
      (libsource (lib "eagle-import") (part "1-2834011-2"))
    )
    (comp (ref "J30")
      (value "1-2834011-2")
      (footprint "eagle-import:128340112")
      (fields (field (name "RS_PART_NUMBER") "1649131"))
      (libsource (lib "eagle-import") (part "1-2834011-2"))
    )
    (comp (ref "J31")
      (value "1-2834011-2")
      (footprint "eagle-import:128340112")
      (fields (field (name "RS_PART_NUMBER") "1649131"))
      (libsource (lib "eagle-import") (part "1-2834011-2"))
    )
    (comp (ref "J32")
      (value "1-2834011-2")
      (footprint "eagle-import:128340112")
      (fields (field (name "RS_PART_NUMBER") "1649131"))
      (libsource (lib "eagle-import") (part "1-2834011-2"))
    )
    (comp (ref "J33")
      (value "1-2834011-2")
      (footprint "eagle-import:128340112")
      (fields (field (name "RS_PART_NUMBER") "1649131"))
      (libsource (lib "eagle-import") (part "1-2834011-2"))
    )
    (comp (ref "J34")
      (value "1-2834011-2")
      (footprint "eagle-import:128340112")
      (fields (field (name "RS_PART_NUMBER") "1649131"))
      (libsource (lib "eagle-import") (part "1-2834011-2"))
    )
    (comp (ref "J35")
      (value "1-2834011-2")
      (footprint "eagle-import:128340112")
      (fields (field (name "RS_PART_NUMBER") "1649131"))
      (libsource (lib "eagle-import") (part "1-2834011-2"))
    )
    (comp (ref "J36")
      (value "1-2834011-2")
      (footprint "eagle-import:128340112")
      (fields (field (name "RS_PART_NUMBER") "1649131"))
      (libsource (lib "eagle-import") (part "1-2834011-2"))
    )
    (comp (ref "J37")
      (value "1-2834011-2")
      (footprint "eagle-import:128340112")
      (fields (field (name "RS_PART_NUMBER") "1649131"))
      (libsource (lib "eagle-import") (part "1-2834011-2"))
    )
    (comp (ref "J43")
      (value "455-1750-1-ND")
      (footprint "eagle-import:1X03")
      (libsource (lib "eagle-import") (part "CONN_03"))
    )
    (comp (ref "J45")
      (value "1-2834011-2")
      (footprint "eagle-import:128340112")
      (fields (field (name "RS_PART_NUMBER") "1649131"))
      (libsource (lib "eagle-import") (part "1-2834011-2"))
    )
    (comp (ref "J46")
      (value "1-2834011-2")
      (footprint "eagle-import:128340112")
      (fields (field (name "RS_PART_NUMBER") "1649131"))
      (libsource (lib "eagle-import") (part "1-2834011-2"))
    )
    (comp (ref "J47")
      (value "1-2834011-2")
      (footprint "eagle-import:128340112")
      (fields (field (name "RS_PART_NUMBER") "1649131"))
      (libsource (lib "eagle-import") (part "1-2834011-2"))
    )
    (comp (ref "J48")
      (value "1-2834011-2")
      (footprint "eagle-import:128340112")
      (fields (field (name "RS_PART_NUMBER") "1649131"))
      (libsource (lib "eagle-import") (part "1-2834011-2"))
    )
    (comp (ref "J49")
      (value "1-2834011-2")
      (footprint "eagle-import:128340112")
      (fields (field (name "RS_PART_NUMBER") "1649131"))
      (libsource (lib "eagle-import") (part "1-2834011-2"))
    )
    (comp (ref "J50")
      (value "1-2834011-2")
      (footprint "eagle-import:128340112")
      (fields (field (name "RS_PART_NUMBER") "1649131"))
      (libsource (lib "eagle-import") (part "1-2834011-2"))
    )
    (comp (ref "J51")
      (value "1-2834011-2")
      (footprint "eagle-import:128340112")
      (fields (field (name "RS_PART_NUMBER") "1649131"))
      (libsource (lib "eagle-import") (part "1-2834011-2"))
    )
    (comp (ref "J52")
      (value "1-2834011-2")
      (footprint "eagle-import:128340112")
      (fields (field (name "RS_PART_NUMBER") "1649131"))
      (libsource (lib "eagle-import") (part "1-2834011-2"))
    )
    (comp (ref "J53")
      (value "455-1750-1-ND")
      (footprint "eagle-import:1X03")
      (libsource (lib "eagle-import") (part "CONN_03"))
    )
    (comp (ref "P1")
      (value "1803277")
      (footprint "eagle-import:PHOENIX_1803277")
      (fields (field (name "MF") "Phoenix Contact"))
      (libsource (lib "eagle-import") (part "1803277"))
    )
    (comp (ref "P2")
      (value "1803277")
      (footprint "eagle-import:PHOENIX_1803277")
      (fields (field (name "MF") "Phoenix Contact"))
      (libsource (lib "eagle-import") (part "1803277"))
    )
    (comp (ref "P3")
      (value "1803277")
      (footprint "eagle-import:PHOENIX_1803277")
      (fields (field (name "MF") "Phoenix Contact"))
      (libsource (lib "eagle-import") (part "1803277"))
    )
    (comp (ref "P4")
      (value "1803277")
      (footprint "eagle-import:PHOENIX_1803277")
      (fields (field (name "MF") "Phoenix Contact"))
      (libsource (lib "eagle-import") (part "1803277"))
    )
    (comp (ref "P5")
      (value "1803277")
      (footprint "eagle-import:PHOENIX_1803277")
      (fields (field (name "MF") "Phoenix Contact"))
      (libsource (lib "eagle-import") (part "1803277"))
    )
    (comp (ref "P6")
      (value "1803277")
      (footprint "eagle-import:PHOENIX_1803277")
      (fields (field (name "MF") "Phoenix Contact"))
      (libsource (lib "eagle-import") (part "1803277"))
    )
    (comp (ref "P7")
      (value "1803277")
      (footprint "eagle-import:PHOENIX_1803277")
      (fields (field (name "MF") "Phoenix Contact"))
      (libsource (lib "eagle-import") (part "1803277"))
    )
  )
  (nets
    (net (code "1") (name "0_DIRECTION") (class "Default")
      (node (ref "J10") (pin "2") (pinfunction "2_2") (pintype "bidirectional"))
      (node (ref "R6") (pin "1") (pinfunction "1_1") (pintype "passive"))
      (node (ref "U1") (pin "13") (pinfunction "E2_13") (pintype "passive"))
    )
    (net (code "2") (name "0_ENABLE") (class "Default")
      (node (ref "J10") (pin "1") (pinfunction "1_1") (pintype "bidirectional"))
      (node (ref "R5") (pin "1") (pinfunction "1_1") (pintype "passive"))
      (node (ref "U1") (pin "15") (pinfunction "E1_15") (pintype "passive"))
    )
    (net (code "3") (name "0_PWM") (class "Default")
      (node (ref "J15") (pin "1") (pinfunction "1_1") (pintype "bidirectional"))
      (node (ref "R7") (pin "1") (pinfunction "1_1") (pintype "passive"))
      (node (ref "U1") (pin "11") (pinfunction "E3_11") (pintype "passive"))
    )
    (net (code "4") (name "1_DIRECTION") (class "Default")
      (node (ref "J11") (pin "1") (pinfunction "1_1") (pintype "bidirectional"))
      (node (ref "R13") (pin "1") (pinfunction "1_1") (pintype "passive"))
      (node (ref "U5") (pin "15") (pinfunction "E1_15") (pintype "passive"))
    )
    (net (code "5") (name "1_ENABLE") (class "Default")
      (node (ref "J15") (pin "2") (pinfunction "2_2") (pintype "bidirectional"))
      (node (ref "R8") (pin "1") (pinfunction "1_1") (pintype "passive"))
      (node (ref "U1") (pin "9") (pinfunction "E4_9") (pintype "passive"))
    )
    (net (code "6") (name "1_PWM") (class "Default")
      (node (ref "J11") (pin "2") (pinfunction "2_2") (pintype "bidirectional"))
      (node (ref "R14") (pin "1") (pinfunction "1_1") (pintype "passive"))
      (node (ref "U5") (pin "13") (pinfunction "E2_13") (pintype "passive"))
    )
    (net (code "7") (name "2_DIRECTION") (class "Default")
      (node (ref "J16") (pin "2") (pinfunction "2_2") (pintype "bidirectional"))
      (node (ref "R16") (pin "1") (pinfunction "1_1") (pintype "passive"))
      (node (ref "U5") (pin "9") (pinfunction "E4_9") (pintype "passive"))
    )
    (net (code "8") (name "2_ENABLE") (class "Default")
      (node (ref "J16") (pin "1") (pinfunction "1_1") (pintype "bidirectional"))
      (node (ref "R15") (pin "1") (pinfunction "1_1") (pintype "passive"))
      (node (ref "U5") (pin "11") (pinfunction "E3_11") (pintype "passive"))
    )
    (net (code "9") (name "2_PWM") (class "Default")
      (node (ref "J12") (pin "1") (pinfunction "1_1") (pintype "bidirectional"))
      (node (ref "R21") (pin "1") (pinfunction "1_1") (pintype "passive"))
      (node (ref "U6") (pin "15") (pinfunction "E1_15") (pintype "passive"))
    )
    (net (code "10") (name "3.3V") (class "Default")
      (node (ref "C2") (pin "1") (pinfunction "P$1_1") (pintype "passive"))
      (node (ref "J1") (pin "29") (pinfunction "29_29") (pintype "passive"))
      (node (ref "J3") (pin "4") (pinfunction "VCC_4") (pintype "passive"))
      (node (ref "J44") (pin "1") (pinfunction "1_1") (pintype "passive"))
      (node (ref "J53") (pin "1") (pinfunction "1_1") (pintype "passive"))
      (node (ref "U10") (pin "4") (pinfunction "CO1_4") (pintype "passive"))
      (node (ref "U3") (pin "1") (pinfunction "VCCA_1") (pintype "bidirectional"))
      (node (ref "U7") (pin "10") (pinfunction "CO4_10") (pintype "passive"))
      (node (ref "U7") (pin "12") (pinfunction "CO3_12") (pintype "passive"))
      (node (ref "U7") (pin "14") (pinfunction "CO2_14") (pintype "passive"))
      (node (ref "U7") (pin "16") (pinfunction "CO1_16") (pintype "passive"))
      (node (ref "U8") (pin "10") (pinfunction "CO4_10") (pintype "passive"))
      (node (ref "U8") (pin "12") (pinfunction "CO3_12") (pintype "passive"))
      (node (ref "U8") (pin "14") (pinfunction "CO2_14") (pintype "passive"))
      (node (ref "U8") (pin "16") (pinfunction "CO1_16") (pintype "passive"))
    )
    (net (code "11") (name "3.3V_ANALOG") (class "Default")
      (node (ref "J43") (pin "1") (pinfunction "1_1") (pintype "passive"))
      (node (ref "P4") (pin "2") (pinfunction "2_2") (pintype "passive"))
    )
    (net (code "12") (name "3_DIRECTION") (class "Default")
      (node (ref "J17") (pin "1") (pinfunction "1_1") (pintype "bidirectional"))
      (node (ref "R23") (pin "1") (pinfunction "1_1") (pintype "passive"))
      (node (ref "U6") (pin "11") (pinfunction "E3_11") (pintype "passive"))
    )
    (net (code "13") (name "3_ENABLE") (class "Default")
      (node (ref "J12") (pin "2") (pinfunction "2_2") (pintype "bidirectional"))
      (node (ref "R22") (pin "1") (pinfunction "1_1") (pintype "passive"))
      (node (ref "U6") (pin "13") (pinfunction "E2_13") (pintype "passive"))
    )
    (net (code "14") (name "3_PWM") (class "Default")
      (node (ref "J17") (pin "2") (pinfunction "2_2") (pintype "bidirectional"))
      (node (ref "R24") (pin "1") (pinfunction "1_1") (pintype "passive"))
      (node (ref "U6") (pin "9") (pinfunction "E4_9") (pintype "passive"))
    )
    (net (code "15") (name "5V") (class "Default")
      (node (ref "C1") (pin "1") (pinfunction "P$1_1") (pintype "passive"))
      (node (ref "C3") (pin "1") (pinfunction "P$1_1") (pintype "passive"))
      (node (ref "J1") (pin "11") (pinfunction "11_11") (pintype "passive"))
      (node (ref "J38") (pin "1") (pinfunction "1_1") (pintype "passive"))
      (node (ref "J44") (pin "3") (pinfunction "3_3") (pintype "passive"))
      (node (ref "J53") (pin "3") (pinfunction "3_3") (pintype "passive"))
      (node (ref "U2") (pin "16") (pinfunction "VDD_16") (pintype "power_in"))
      (node (ref "U3") (pin "14") (pinfunction "VCCB_14") (pintype "bidirectional"))
      (node (ref "U3") (pin "8") (pinfunction "OE_8") (pintype "bidirectional"))
    )
    (net (code "16") (name "5V_ANALOG") (class "Default")
      (node (ref "J43") (pin "3") (pinfunction "3_3") (pintype "passive"))
      (node (ref "P6") (pin "2") (pinfunction "2_2") (pintype "passive"))
    )
    (net (code "17") (name "12V") (class "Default")
      (node (ref "J36") (pin "1") (pinfunction "1_1") (pintype "bidirectional"))
      (node (ref "J36") (pin "2") (pinfunction "2_2") (pintype "bidirectional"))
      (node (ref "J37") (pin "1") (pinfunction "1_1") (pintype "bidirectional"))
      (node (ref "J37") (pin "2") (pinfunction "2_2") (pintype "bidirectional"))
      (node (ref "P1") (pin "2") (pinfunction "2_2") (pintype "passive"))
      (node (ref "P3") (pin "2") (pinfunction "2_2") (pintype "passive"))
      (node (ref "P5") (pin "2") (pinfunction "2_2") (pintype "passive"))
      (node (ref "P7") (pin "2") (pinfunction "2_2") (pintype "passive"))
    )
    (net (code "18") (name "12V_ANALOG") (class "Default")
      (node (ref "P2") (pin "2") (pinfunction "2_2") (pintype "passive"))
      (node (ref "P3") (pin "1") (pinfunction "1_1") (pintype "passive"))
    )
    (net (code "19") (name "ADC_0") (class "Default")
      (node (ref "J23") (pin "1") (pinfunction "1_1") (pintype "bidirectional"))
      (node (ref "J38") (pin "2") (pinfunction "2_2") (pintype "passive"))
      (node (ref "U2") (pin "1") (pinfunction "CH0_1") (pintype "input"))
    )
    (net (code "20") (name "ADC_1") (class "Default")
      (node (ref "J23") (pin "2") (pinfunction "2_2") (pintype "bidirectional"))
      (node (ref "J38") (pin "3") (pinfunction "3_3") (pintype "passive"))
      (node (ref "U2") (pin "2") (pinfunction "CH1_2") (pintype "input"))
    )
    (net (code "21") (name "ADC_2") (class "Default")
      (node (ref "J22") (pin "1") (pinfunction "1_1") (pintype "bidirectional"))
      (node (ref "J38") (pin "4") (pinfunction "4_4") (pintype "passive"))
      (node (ref "U2") (pin "3") (pinfunction "CH2_3") (pintype "input"))
    )
    (net (code "22") (name "ADC_3") (class "Default")
      (node (ref "J22") (pin "2") (pinfunction "2_2") (pintype "bidirectional"))
      (node (ref "J38") (pin "5") (pinfunction "5_5") (pintype "passive"))
      (node (ref "U2") (pin "4") (pinfunction "CH3_4") (pintype "input"))
    )
    (net (code "23") (name "ADC_4") (class "Default")
      (node (ref "J21") (pin "1") (pinfunction "1_1") (pintype "bidirectional"))
      (node (ref "J38") (pin "6") (pinfunction "6_6") (pintype "passive"))
      (node (ref "U2") (pin "5") (pinfunction "CH4_5") (pintype "input"))
    )
    (net (code "24") (name "ADC_5") (class "Default")
      (node (ref "J21") (pin "2") (pinfunction "2_2") (pintype "bidirectional"))
      (node (ref "J38") (pin "7") (pinfunction "7_7") (pintype "passive"))
      (node (ref "U2") (pin "6") (pinfunction "CH5_6") (pintype "input"))
    )
    (net (code "25") (name "ADC_6") (class "Default")
      (node (ref "J20") (pin "1") (pinfunction "1_1") (pintype "bidirectional"))
      (node (ref "J38") (pin "8") (pinfunction "8_8") (pintype "passive"))
      (node (ref "U2") (pin "7") (pinfunction "CH6_7") (pintype "input"))
    )
    (net (code "26") (name "ADC_7") (class "Default")
      (node (ref "J20") (pin "2") (pinfunction "2_2") (pintype "bidirectional"))
      (node (ref "J38") (pin "9") (pinfunction "9_9") (pintype "passive"))
      (node (ref "U2") (pin "8") (pinfunction "CH7_8") (pintype "input"))
    )
    (net (code "27") (name "AGND") (class "Default")
      (node (ref "J32") (pin "1") (pinfunction "1_1") (pintype "bidirectional"))
      (node (ref "J32") (pin "2") (pinfunction "2_2") (pintype "bidirectional"))
      (node (ref "J33") (pin "1") (pinfunction "1_1") (pintype "bidirectional"))
      (node (ref "J33") (pin "2") (pinfunction "2_2") (pintype "bidirectional"))
      (node (ref "J34") (pin "1") (pinfunction "1_1") (pintype "bidirectional"))
      (node (ref "J34") (pin "2") (pinfunction "2_2") (pintype "bidirectional"))
      (node (ref "J35") (pin "1") (pinfunction "1_1") (pintype "bidirectional"))
      (node (ref "J35") (pin "2") (pinfunction "2_2") (pintype "bidirectional"))
      (node (ref "P1") (pin "1") (pinfunction "1_1") (pintype "passive"))
      (node (ref "P2") (pin "1") (pinfunction "1_1") (pintype "passive"))
      (node (ref "P4") (pin "1") (pinfunction "1_1") (pintype "passive"))
      (node (ref "P5") (pin "1") (pinfunction "1_1") (pintype "passive"))
      (node (ref "P6") (pin "1") (pinfunction "1_1") (pintype "passive"))
      (node (ref "P7") (pin "1") (pinfunction "1_1") (pintype "passive"))
      (node (ref "R13") (pin "2") (pinfunction "2_2") (pintype "passive"))
      (node (ref "R14") (pin "2") (pinfunction "2_2") (pintype "passive"))
      (node (ref "R15") (pin "2") (pinfunction "2_2") (pintype "passive"))
      (node (ref "R16") (pin "2") (pinfunction "2_2") (pintype "passive"))
      (node (ref "R21") (pin "2") (pinfunction "2_2") (pintype "passive"))
      (node (ref "R22") (pin "2") (pinfunction "2_2") (pintype "passive"))
      (node (ref "R23") (pin "2") (pinfunction "2_2") (pintype "passive"))
      (node (ref "R24") (pin "2") (pinfunction "2_2") (pintype "passive"))
      (node (ref "R45") (pin "2") (pinfunction "2_2") (pintype "passive"))
      (node (ref "R46") (pin "2") (pinfunction "2_2") (pintype "passive"))
      (node (ref "R47") (pin "2") (pinfunction "2_2") (pintype "passive"))
      (node (ref "R48") (pin "2") (pinfunction "2_2") (pintype "passive"))
      (node (ref "R5") (pin "2") (pinfunction "2_2") (pintype "passive"))
      (node (ref "R51") (pin "1") (pinfunction "1_1") (pintype "passive"))
      (node (ref "R52") (pin "1") (pinfunction "1_1") (pintype "passive"))
      (node (ref "R53") (pin "1") (pinfunction "1_1") (pintype "passive"))
      (node (ref "R54") (pin "1") (pinfunction "1_1") (pintype "passive"))
      (node (ref "R55") (pin "1") (pinfunction "1_1") (pintype "passive"))
      (node (ref "R56") (pin "1") (pinfunction "1_1") (pintype "passive"))
      (node (ref "R57") (pin "2") (pinfunction "2_2") (pintype "passive"))
      (node (ref "R58") (pin "2") (pinfunction "2_2") (pintype "passive"))
      (node (ref "R59") (pin "2") (pinfunction "2_2") (pintype "passive"))
      (node (ref "R6") (pin "2") (pinfunction "2_2") (pintype "passive"))
      (node (ref "R60") (pin "2") (pinfunction "2_2") (pintype "passive"))
      (node (ref "R61") (pin "2") (pinfunction "2_2") (pintype "passive"))
      (node (ref "R62") (pin "2") (pinfunction "2_2") (pintype "passive"))
      (node (ref "R7") (pin "2") (pinfunction "2_2") (pintype "passive"))
      (node (ref "R8") (pin "2") (pinfunction "2_2") (pintype "passive"))
      (node (ref "U10") (pin "2") (pinfunction "C1_2") (pintype "passive"))
      (node (ref "U4") (pin "12") (pinfunction "VSS_12") (pintype "power_in"))
      (node (ref "U4") (pin "15") (pinfunction "INHIBIT_15") (pintype "input"))
      (node (ref "U7") (pin "2") (pinfunction "C1_2") (pintype "passive"))
      (node (ref "U7") (pin "4") (pinfunction "C2_4") (pintype "passive"))
      (node (ref "U7") (pin "6") (pinfunction "C3_6") (pintype "passive"))
      (node (ref "U7") (pin "8") (pinfunction "C4_8") (pintype "passive"))
      (node (ref "U8") (pin "2") (pinfunction "C1_2") (pintype "passive"))
      (node (ref "U8") (pin "4") (pinfunction "C2_4") (pintype "passive"))
      (node (ref "U8") (pin "6") (pinfunction "C3_6") (pintype "passive"))
      (node (ref "U8") (pin "8") (pinfunction "C4_8") (pintype "passive"))
      (node (ref "X1") (pin "2") (pinfunction "2_GND_BLACK_2") (pintype "passive"))
      (node (ref "X1") (pin "3") (pinfunction "3_GND_RED_3") (pintype "passive"))
      (node (ref "X2") (pin "2") (pinfunction "2_GND_BLACK_2") (pintype "passive"))
      (node (ref "X2") (pin "3") (pinfunction "3_GND_RED_3") (pintype "passive"))
      (node (ref "X3") (pin "2") (pinfunction "2_GND_BLACK_2") (pintype "passive"))
      (node (ref "X3") (pin "3") (pinfunction "3_GND_RED_3") (pintype "passive"))
      (node (ref "X4") (pin "2") (pinfunction "2_GND_BLACK_2") (pintype "passive"))
      (node (ref "X4") (pin "3") (pinfunction "3_GND_RED_3") (pintype "passive"))
    )
    (net (code "28") (name "CLK") (class "Default")
      (node (ref "J1") (pin "40") (pinfunction "40_40") (pintype "passive"))
      (node (ref "U3") (pin "5") (pinfunction "A4_5") (pintype "bidirectional"))
    )
    (net (code "29") (name "CS") (class "Default")
      (node (ref "J1") (pin "37") (pinfunction "37_37") (pintype "passive"))
      (node (ref "U3") (pin "2") (pinfunction "A1_2") (pintype "bidirectional"))
    )
    (net (code "30") (name "ENCODER_0_T1") (class "Default")
      (node (ref "J1") (pin "31") (pinfunction "31_31") (pintype "passive"))
      (node (ref "R29") (pin "1") (pinfunction "1_1") (pintype "passive"))
      (node (ref "U7") (pin "15") (pinfunction "E1_15") (pintype "passive"))
    )
    (net (code "31") (name "ENCODER_0_T2") (class "Default")
      (node (ref "J1") (pin "28") (pinfunction "28_28") (pintype "passive"))
      (node (ref "R30") (pin "1") (pinfunction "1_1") (pintype "passive"))
      (node (ref "U7") (pin "13") (pinfunction "E2_13") (pintype "passive"))
    )
    (net (code "32") (name "ENCODER_1_T1") (class "Default")
      (node (ref "J1") (pin "27") (pinfunction "27_27") (pintype "passive"))
      (node (ref "R31") (pin "1") (pinfunction "1_1") (pintype "passive"))
      (node (ref "U7") (pin "11") (pinfunction "E3_11") (pintype "passive"))
    )
    (net (code "33") (name "ENCODER_1_T2") (class "Default")
      (node (ref "J1") (pin "26") (pinfunction "26_26") (pintype "passive"))
      (node (ref "R32") (pin "1") (pinfunction "1_1") (pintype "passive"))
      (node (ref "U7") (pin "9") (pinfunction "E4_9") (pintype "passive"))
    )
    (net (code "34") (name "ENCODER_2_T1") (class "Default")
      (node (ref "J1") (pin "25") (pinfunction "25_25") (pintype "passive"))
      (node (ref "R37") (pin "1") (pinfunction "1_1") (pintype "passive"))
      (node (ref "U8") (pin "15") (pinfunction "E1_15") (pintype "passive"))
    )
    (net (code "35") (name "ENCODER_2_T2") (class "Default")
      (node (ref "J1") (pin "24") (pinfunction "24_24") (pintype "passive"))
      (node (ref "R38") (pin "1") (pinfunction "1_1") (pintype "passive"))
      (node (ref "U8") (pin "13") (pinfunction "E2_13") (pintype "passive"))
    )
    (net (code "36") (name "ENCODER_3_T1") (class "Default")
      (node (ref "J1") (pin "23") (pinfunction "23_23") (pintype "passive"))
      (node (ref "R39") (pin "1") (pinfunction "1_1") (pintype "passive"))
      (node (ref "U8") (pin "11") (pinfunction "E3_11") (pintype "passive"))
    )
    (net (code "37") (name "ENCODER_3_T2") (class "Default")
      (node (ref "J1") (pin "22") (pinfunction "22_22") (pintype "passive"))
      (node (ref "R40") (pin "1") (pinfunction "1_1") (pintype "passive"))
      (node (ref "U8") (pin "9") (pinfunction "E4_9") (pintype "passive"))
    )
    (net (code "38") (name "GND") (class "Default")
      (node (ref "C1") (pin "2") (pinfunction "P$2_2") (pintype "passive"))
      (node (ref "C2") (pin "2") (pinfunction "P$2_2") (pintype "passive"))
      (node (ref "C3") (pin "2") (pinfunction "P$2_2") (pintype "passive"))
      (node (ref "J1") (pin "12") (pinfunction "12_12") (pintype "passive"))
      (node (ref "J1") (pin "30") (pinfunction "30_30") (pintype "passive"))
      (node (ref "J3") (pin "6") (pinfunction "GND_6") (pintype "passive"))
      (node (ref "J38") (pin "10") (pinfunction "10_10") (pintype "passive"))
      (node (ref "J49") (pin "1") (pinfunction "1_1") (pintype "bidirectional"))
      (node (ref "J49") (pin "2") (pinfunction "2_2") (pintype "bidirectional"))
      (node (ref "J50") (pin "1") (pinfunction "1_1") (pintype "bidirectional"))
      (node (ref "J50") (pin "2") (pinfunction "2_2") (pintype "bidirectional"))
      (node (ref "J51") (pin "1") (pinfunction "1_1") (pintype "bidirectional"))
      (node (ref "J51") (pin "2") (pinfunction "2_2") (pintype "bidirectional"))
      (node (ref "J52") (pin "1") (pinfunction "1_1") (pintype "bidirectional"))
      (node (ref "J52") (pin "2") (pinfunction "2_2") (pintype "bidirectional"))
      (node (ref "R29") (pin "2") (pinfunction "2_2") (pintype "passive"))
      (node (ref "R30") (pin "2") (pinfunction "2_2") (pintype "passive"))
      (node (ref "R31") (pin "2") (pinfunction "2_2") (pintype "passive"))
      (node (ref "R32") (pin "2") (pinfunction "2_2") (pintype "passive"))
      (node (ref "R37") (pin "2") (pinfunction "2_2") (pintype "passive"))
      (node (ref "R38") (pin "2") (pinfunction "2_2") (pintype "passive"))
      (node (ref "R39") (pin "2") (pinfunction "2_2") (pintype "passive"))
      (node (ref "R40") (pin "2") (pinfunction "2_2") (pintype "passive"))
      (node (ref "R50") (pin "2") (pinfunction "2_2") (pintype "passive"))
      (node (ref "U1") (pin "2") (pinfunction "C1_2") (pintype "passive"))
      (node (ref "U1") (pin "4") (pinfunction "C2_4") (pintype "passive"))
      (node (ref "U1") (pin "6") (pinfunction "C3_6") (pintype "passive"))
      (node (ref "U1") (pin "8") (pinfunction "C4_8") (pintype "passive"))
      (node (ref "U2") (pin "14") (pinfunction "AGND_14") (pintype "passive"))
      (node (ref "U2") (pin "9") (pinfunction "DGND_9") (pintype "passive"))
      (node (ref "U3") (pin "7") (pinfunction "GND_7") (pintype "bidirectional"))
      (node (ref "U5") (pin "2") (pinfunction "C1_2") (pintype "passive"))
      (node (ref "U5") (pin "4") (pinfunction "C2_4") (pintype "passive"))
      (node (ref "U5") (pin "6") (pinfunction "C3_6") (pintype "passive"))
      (node (ref "U5") (pin "8") (pinfunction "C4_8") (pintype "passive"))
      (node (ref "U6") (pin "2") (pinfunction "C1_2") (pintype "passive"))
      (node (ref "U6") (pin "4") (pinfunction "C2_4") (pintype "passive"))
      (node (ref "U6") (pin "6") (pinfunction "C3_6") (pintype "passive"))
      (node (ref "U6") (pin "8") (pinfunction "C4_8") (pintype "passive"))
      (node (ref "U9") (pin "2") (pinfunction "C1_2") (pintype "passive"))
      (node (ref "U9") (pin "4") (pinfunction "C2_4") (pintype "passive"))
      (node (ref "U9") (pin "6") (pinfunction "C3_6") (pintype "passive"))
      (node (ref "U9") (pin "8") (pinfunction "C4_8") (pintype "passive"))
    )
    (net (code "39") (name "MISO") (class "Default")
      (node (ref "J1") (pin "39") (pinfunction "39_39") (pintype "passive"))
      (node (ref "U3") (pin "4") (pinfunction "A3_4") (pintype "bidirectional"))
    )
    (net (code "40") (name "MOSI") (class "Default")
      (node (ref "J1") (pin "38") (pinfunction "38_38") (pintype "passive"))
      (node (ref "U3") (pin "3") (pinfunction "A2_3") (pintype "bidirectional"))
    )
    (net (code "41") (name "MOTOR_0_DIR") (class "Default")
      (node (ref "J1") (pin "15") (pinfunction "15_15") (pintype "passive"))
      (node (ref "R2") (pin "1") (pinfunction "1_1") (pintype "passive"))
    )
    (net (code "42") (name "MOTOR_0_EN") (class "Default")
      (node (ref "J1") (pin "16") (pinfunction "16_16") (pintype "passive"))
      (node (ref "R1") (pin "1") (pinfunction "1_1") (pintype "passive"))
    )
    (net (code "43") (name "MOTOR_0_PWM") (class "Default")
      (node (ref "J1") (pin "14") (pinfunction "14_14") (pintype "passive"))
      (node (ref "R3") (pin "1") (pinfunction "1_1") (pintype "passive"))
    )
    (net (code "44") (name "MOTOR_0_T1") (class "Default")
      (node (ref "J18") (pin "1") (pinfunction "1_1") (pintype "bidirectional"))
      (node (ref "R25") (pin "1") (pinfunction "1_1") (pintype "passive"))
    )
    (net (code "45") (name "MOTOR_0_T2") (class "Default")
      (node (ref "J13") (pin "1") (pinfunction "1_1") (pintype "bidirectional"))
      (node (ref "R26") (pin "1") (pinfunction "1_1") (pintype "passive"))
    )
    (net (code "46") (name "MOTOR_1_DIR") (class "Default")
      (node (ref "J1") (pin "10") (pinfunction "10_10") (pintype "passive"))
      (node (ref "R9") (pin "1") (pinfunction "1_1") (pintype "passive"))
    )
    (net (code "47") (name "MOTOR_1_EN") (class "Default")
      (node (ref "J1") (pin "13") (pinfunction "13_13") (pintype "passive"))
      (node (ref "R4") (pin "1") (pinfunction "1_1") (pintype "passive"))
    )
    (net (code "48") (name "MOTOR_1_PWM") (class "Default")
      (node (ref "J1") (pin "9") (pinfunction "9_9") (pintype "passive"))
      (node (ref "R10") (pin "1") (pinfunction "1_1") (pintype "passive"))
    )
    (net (code "49") (name "MOTOR_1_T1") (class "Default")
      (node (ref "J18") (pin "2") (pinfunction "2_2") (pintype "bidirectional"))
      (node (ref "R27") (pin "1") (pinfunction "1_1") (pintype "passive"))
    )
    (net (code "50") (name "MOTOR_1_T2") (class "Default")
      (node (ref "J13") (pin "2") (pinfunction "2_2") (pintype "bidirectional"))
      (node (ref "R28") (pin "1") (pinfunction "1_1") (pintype "passive"))
    )
    (net (code "51") (name "MOTOR_2_DIR") (class "Default")
      (node (ref "J1") (pin "7") (pinfunction "7_7") (pintype "passive"))
      (node (ref "R12") (pin "1") (pinfunction "1_1") (pintype "passive"))
    )
    (net (code "52") (name "MOTOR_2_EN") (class "Default")
      (node (ref "J1") (pin "8") (pinfunction "8_8") (pintype "passive"))
      (node (ref "R11") (pin "1") (pinfunction "1_1") (pintype "passive"))
    )
    (net (code "53") (name "MOTOR_2_PWM") (class "Default")
      (node (ref "J1") (pin "6") (pinfunction "6_6") (pintype "passive"))
      (node (ref "R17") (pin "1") (pinfunction "1_1") (pintype "passive"))
    )
    (net (code "54") (name "MOTOR_2_T1") (class "Default")
      (node (ref "J19") (pin "1") (pinfunction "1_1") (pintype "bidirectional"))
      (node (ref "R33") (pin "1") (pinfunction "1_1") (pintype "passive"))
    )
    (net (code "55") (name "MOTOR_2_T2") (class "Default")
      (node (ref "J14") (pin "1") (pinfunction "1_1") (pintype "bidirectional"))
      (node (ref "R34") (pin "1") (pinfunction "1_1") (pintype "passive"))
    )
    (net (code "56") (name "MOTOR_3_DIR") (class "Default")
      (node (ref "J1") (pin "4") (pinfunction "4_4") (pintype "passive"))
      (node (ref "R19") (pin "1") (pinfunction "1_1") (pintype "passive"))
    )
    (net (code "57") (name "MOTOR_3_EN") (class "Default")
      (node (ref "J1") (pin "5") (pinfunction "5_5") (pintype "passive"))
      (node (ref "R18") (pin "1") (pinfunction "1_1") (pintype "passive"))
    )
    (net (code "58") (name "MOTOR_3_PWM") (class "Default")
      (node (ref "J1") (pin "3") (pinfunction "3_3") (pintype "passive"))
      (node (ref "R20") (pin "1") (pinfunction "1_1") (pintype "passive"))
    )
    (net (code "59") (name "MOTOR_3_T1") (class "Default")
      (node (ref "J19") (pin "2") (pinfunction "2_2") (pintype "bidirectional"))
      (node (ref "R35") (pin "1") (pinfunction "1_1") (pintype "passive"))
    )
    (net (code "60") (name "MOTOR_3_T2") (class "Default")
      (node (ref "J14") (pin "2") (pinfunction "2_2") (pintype "bidirectional"))
      (node (ref "R36") (pin "1") (pinfunction "1_1") (pintype "passive"))
    )
    (net (code "61") (name "MUX_0") (class "Default")
      (node (ref "R66") (pin "2") (pinfunction "2_2") (pintype "passive"))
      (node (ref "U4") (pin "9") (pinfunction "X0_9") (pintype "bidirectional"))
      (node (ref "X4") (pin "1") (pinfunction "1_ANA_WHITE_1") (pintype "passive"))
    )
    (net (code "62") (name "MUX_1") (class "Default")
      (node (ref "R65") (pin "2") (pinfunction "2_2") (pintype "passive"))
      (node (ref "U4") (pin "8") (pinfunction "X1_8") (pintype "bidirectional"))
      (node (ref "X3") (pin "1") (pinfunction "1_ANA_WHITE_1") (pintype "passive"))
    )
    (net (code "63") (name "MUX_2") (class "Default")
      (node (ref "R63") (pin "2") (pinfunction "2_2") (pintype "passive"))
      (node (ref "U4") (pin "7") (pinfunction "X2_7") (pintype "bidirectional"))
      (node (ref "X2") (pin "1") (pinfunction "1_ANA_WHITE_1") (pintype "passive"))
    )
    (net (code "64") (name "MUX_3") (class "Default")
      (node (ref "R64") (pin "2") (pinfunction "2_2") (pintype "passive"))
      (node (ref "U4") (pin "6") (pinfunction "X3_6") (pintype "bidirectional"))
      (node (ref "X1") (pin "1") (pinfunction "1_ANA_WHITE_1") (pintype "passive"))
    )
    (net (code "65") (name "MUX_4") (class "Default")
      (node (ref "J9") (pin "2") (pinfunction "2_2") (pintype "bidirectional"))
      (node (ref "R62") (pin "1") (pinfunction "1_1") (pintype "passive"))
      (node (ref "U4") (pin "5") (pinfunction "X5_5") (pintype "bidirectional"))
    )
    (net (code "66") (name "MUX_5") (class "Default")
      (node (ref "J9") (pin "1") (pinfunction "1_1") (pintype "bidirectional"))
      (node (ref "R56") (pin "2") (pinfunction "2_2") (pintype "passive"))
      (node (ref "U4") (pin "4") (pinfunction "X5_2_4") (pintype "bidirectional"))
    )
    (net (code "67") (name "MUX_6") (class "Default")
      (node (ref "J8") (pin "2") (pinfunction "2_2") (pintype "bidirectional"))
      (node (ref "R61") (pin "1") (pinfunction "1_1") (pintype "passive"))
      (node (ref "U4") (pin "3") (pinfunction "X6_3") (pintype "bidirectional"))
    )
    (net (code "68") (name "MUX_7") (class "Default")
      (node (ref "J8") (pin "1") (pinfunction "1_1") (pintype "bidirectional"))
      (node (ref "R55") (pin "2") (pinfunction "2_2") (pintype "passive"))
      (node (ref "U4") (pin "2") (pinfunction "X7_2") (pintype "bidirectional"))
    )
    (net (code "69") (name "MUX_8") (class "Default")
      (node (ref "J7") (pin "2") (pinfunction "2_2") (pintype "bidirectional"))
      (node (ref "R60") (pin "1") (pinfunction "1_1") (pintype "passive"))
      (node (ref "U4") (pin "23") (pinfunction "X8_23") (pintype "bidirectional"))
    )
    (net (code "70") (name "MUX_9") (class "Default")
      (node (ref "J7") (pin "1") (pinfunction "1_1") (pintype "bidirectional"))
      (node (ref "R54") (pin "2") (pinfunction "2_2") (pintype "passive"))
      (node (ref "U4") (pin "22") (pinfunction "X9_22") (pintype "bidirectional"))
    )
    (net (code "71") (name "MUX_10") (class "Default")
      (node (ref "J6") (pin "2") (pinfunction "2_2") (pintype "bidirectional"))
      (node (ref "R59") (pin "1") (pinfunction "1_1") (pintype "passive"))
      (node (ref "U4") (pin "21") (pinfunction "X10_21") (pintype "bidirectional"))
    )
    (net (code "72") (name "MUX_11") (class "Default")
      (node (ref "J6") (pin "1") (pinfunction "1_1") (pintype "bidirectional"))
      (node (ref "R53") (pin "2") (pinfunction "2_2") (pintype "passive"))
      (node (ref "U4") (pin "20") (pinfunction "X11_20") (pintype "bidirectional"))
    )
    (net (code "73") (name "MUX_12") (class "Default")
      (node (ref "J5") (pin "2") (pinfunction "2_2") (pintype "bidirectional"))
      (node (ref "R58") (pin "1") (pinfunction "1_1") (pintype "passive"))
      (node (ref "U4") (pin "19") (pinfunction "X12_19") (pintype "bidirectional"))
    )
    (net (code "74") (name "MUX_13") (class "Default")
      (node (ref "J5") (pin "1") (pinfunction "1_1") (pintype "bidirectional"))
      (node (ref "R52") (pin "2") (pinfunction "2_2") (pintype "passive"))
      (node (ref "U4") (pin "18") (pinfunction "X13_18") (pintype "bidirectional"))
    )
    (net (code "75") (name "MUX_14") (class "Default")
      (node (ref "J4") (pin "2") (pinfunction "2_2") (pintype "bidirectional"))
      (node (ref "R57") (pin "1") (pinfunction "1_1") (pintype "passive"))
      (node (ref "U4") (pin "17") (pinfunction "X14_17") (pintype "bidirectional"))
    )
    (net (code "76") (name "MUX_15") (class "Default")
      (node (ref "J4") (pin "1") (pinfunction "1_1") (pintype "bidirectional"))
      (node (ref "R51") (pin "2") (pinfunction "2_2") (pintype "passive"))
      (node (ref "U4") (pin "16") (pinfunction "X15_16") (pintype "bidirectional"))
    )
    (net (code "77") (name "MUX_A") (class "Default")
      (node (ref "J1") (pin "18") (pinfunction "18_18") (pintype "passive"))
      (node (ref "R41") (pin "1") (pinfunction "1_1") (pintype "passive"))
    )
    (net (code "78") (name "MUX_A_ANALOG") (class "Default")
      (node (ref "R45") (pin "1") (pinfunction "1_1") (pintype "passive"))
      (node (ref "U4") (pin "10") (pinfunction "A_10") (pintype "input"))
      (node (ref "U9") (pin "15") (pinfunction "E1_15") (pintype "passive"))
    )
    (net (code "79") (name "MUX_B") (class "Default")
      (node (ref "J1") (pin "19") (pinfunction "19_19") (pintype "passive"))
      (node (ref "R42") (pin "1") (pinfunction "1_1") (pintype "passive"))
    )
    (net (code "80") (name "MUX_B_ANALOG") (class "Default")
      (node (ref "R46") (pin "1") (pinfunction "1_1") (pintype "passive"))
      (node (ref "U4") (pin "11") (pinfunction "B_11") (pintype "input"))
      (node (ref "U9") (pin "13") (pinfunction "E2_13") (pintype "passive"))
    )
    (net (code "81") (name "MUX_C") (class "Default")
      (node (ref "J1") (pin "20") (pinfunction "20_20") (pintype "passive"))
      (node (ref "R43") (pin "1") (pinfunction "1_1") (pintype "passive"))
    )
    (net (code "82") (name "MUX_C_ANALOG") (class "Default")
      (node (ref "R47") (pin "1") (pinfunction "1_1") (pintype "passive"))
      (node (ref "U4") (pin "14") (pinfunction "C_14") (pintype "input"))
      (node (ref "U9") (pin "11") (pinfunction "E3_11") (pintype "passive"))
    )
    (net (code "83") (name "MUX_D") (class "Default")
      (node (ref "J1") (pin "21") (pinfunction "21_21") (pintype "passive"))
      (node (ref "R44") (pin "1") (pinfunction "1_1") (pintype "passive"))
    )
    (net (code "84") (name "MUX_D_ANALOG") (class "Default")
      (node (ref "R48") (pin "1") (pinfunction "1_1") (pintype "passive"))
      (node (ref "U4") (pin "13") (pinfunction "D_13") (pintype "input"))
      (node (ref "U9") (pin "9") (pinfunction "E4_9") (pintype "passive"))
    )
    (net (code "85") (name "MUX_OUT") (class "Default")
      (node (ref "J1") (pin "17") (pinfunction "17_17") (pintype "passive"))
      (node (ref "R50") (pin "1") (pinfunction "1_1") (pintype "passive"))
      (node (ref "U10") (pin "3") (pinfunction "E1_3") (pintype "passive"))
    )
    (net (code "86") (name "N$3") (class "Default")
      (node (ref "J1") (pin "36") (pinfunction "36_36") (pintype "passive"))
    )
    (net (code "87") (name "N$4") (class "Default")
      (node (ref "J1") (pin "34") (pinfunction "34_34") (pintype "passive"))
    )
    (net (code "88") (name "N$5") (class "Default")
      (node (ref "J1") (pin "32") (pinfunction "32_32") (pintype "passive"))
    )
    (net (code "89") (name "N$37") (class "Default")
      (node (ref "J1") (pin "33") (pinfunction "33_33") (pintype "passive"))
    )
    (net (code "90") (name "N$38") (class "Default")
      (node (ref "J1") (pin "35") (pinfunction "35_35") (pintype "passive"))
    )
    (net (code "91") (name "Net-(U1-A1)") (class "Default")
      (node (ref "R1") (pin "2") (pinfunction "2_2") (pintype "passive"))
      (node (ref "U1") (pin "1") (pinfunction "A1_1") (pintype "passive"))
    )
    (net (code "92") (name "Net-(U1-A2)") (class "Default")
      (node (ref "R2") (pin "2") (pinfunction "2_2") (pintype "passive"))
      (node (ref "U1") (pin "3") (pinfunction "A2_3") (pintype "passive"))
    )
    (net (code "93") (name "Net-(U1-A3)") (class "Default")
      (node (ref "R3") (pin "2") (pinfunction "2_2") (pintype "passive"))
      (node (ref "U1") (pin "5") (pinfunction "A3_5") (pintype "passive"))
    )
    (net (code "94") (name "Net-(U1-A4)") (class "Default")
      (node (ref "R4") (pin "2") (pinfunction "2_2") (pintype "passive"))
      (node (ref "U1") (pin "7") (pinfunction "A4_7") (pintype "passive"))
    )
    (net (code "95") (name "Net-(U2-*CS{slash}SHDN)") (class "Default")
      (node (ref "U2") (pin "10") (pinfunction "*CS/SHDN_10") (pintype "input"))
      (node (ref "U3") (pin "13") (pinfunction "B1_13") (pintype "bidirectional"))
    )
    (net (code "96") (name "Net-(U2-CLK)") (class "Default")
      (node (ref "U2") (pin "13") (pinfunction "CLK_13") (pintype "input"))
      (node (ref "U3") (pin "10") (pinfunction "B4_10") (pintype "bidirectional"))
    )
    (net (code "97") (name "Net-(U2-DIN)") (class "Default")
      (node (ref "U2") (pin "11") (pinfunction "DIN_11") (pintype "input"))
      (node (ref "U3") (pin "12") (pinfunction "B2_12") (pintype "bidirectional"))
    )
    (net (code "98") (name "Net-(U2-DOUT)") (class "Default")
      (node (ref "U2") (pin "12") (pinfunction "DOUT_12") (pintype "output"))
      (node (ref "U3") (pin "11") (pinfunction "B3_11") (pintype "bidirectional"))
    )
    (net (code "99") (name "Net-(U2-VREF)") (class "Default")
      (node (ref "J44") (pin "2") (pinfunction "2_2") (pintype "passive"))
      (node (ref "U2") (pin "15") (pinfunction "VREF_15") (pintype "input"))
    )
    (net (code "100") (name "Net-(U4-X)") (class "Default")
      (node (ref "R49") (pin "1") (pinfunction "1_1") (pintype "passive"))
      (node (ref "U4") (pin "1") (pinfunction "X_1") (pintype "bidirectional"))
    )
    (net (code "101") (name "Net-(U5-A1)") (class "Default")
      (node (ref "R9") (pin "2") (pinfunction "2_2") (pintype "passive"))
      (node (ref "U5") (pin "1") (pinfunction "A1_1") (pintype "passive"))
    )
    (net (code "102") (name "Net-(U5-A2)") (class "Default")
      (node (ref "R10") (pin "2") (pinfunction "2_2") (pintype "passive"))
      (node (ref "U5") (pin "3") (pinfunction "A2_3") (pintype "passive"))
    )
    (net (code "103") (name "Net-(U5-A3)") (class "Default")
      (node (ref "R11") (pin "2") (pinfunction "2_2") (pintype "passive"))
      (node (ref "U5") (pin "5") (pinfunction "A3_5") (pintype "passive"))
    )
    (net (code "104") (name "Net-(U5-A4)") (class "Default")
      (node (ref "R12") (pin "2") (pinfunction "2_2") (pintype "passive"))
      (node (ref "U5") (pin "7") (pinfunction "A4_7") (pintype "passive"))
    )
    (net (code "105") (name "Net-(U6-A1)") (class "Default")
      (node (ref "R17") (pin "2") (pinfunction "2_2") (pintype "passive"))
      (node (ref "U6") (pin "1") (pinfunction "A1_1") (pintype "passive"))
    )
    (net (code "106") (name "Net-(U6-A2)") (class "Default")
      (node (ref "R18") (pin "2") (pinfunction "2_2") (pintype "passive"))
      (node (ref "U6") (pin "3") (pinfunction "A2_3") (pintype "passive"))
    )
    (net (code "107") (name "Net-(U6-A3)") (class "Default")
      (node (ref "R19") (pin "2") (pinfunction "2_2") (pintype "passive"))
      (node (ref "U6") (pin "5") (pinfunction "A3_5") (pintype "passive"))
    )
    (net (code "108") (name "Net-(U6-A4)") (class "Default")
      (node (ref "R20") (pin "2") (pinfunction "2_2") (pintype "passive"))
      (node (ref "U6") (pin "7") (pinfunction "A4_7") (pintype "passive"))
    )
    (net (code "109") (name "Net-(U7-A1)") (class "Default")
      (node (ref "R25") (pin "2") (pinfunction "2_2") (pintype "passive"))
      (node (ref "U7") (pin "1") (pinfunction "A1_1") (pintype "passive"))
    )
    (net (code "110") (name "Net-(U7-A2)") (class "Default")
      (node (ref "R26") (pin "2") (pinfunction "2_2") (pintype "passive"))
      (node (ref "U7") (pin "3") (pinfunction "A2_3") (pintype "passive"))
    )
    (net (code "111") (name "Net-(U7-A3)") (class "Default")
      (node (ref "R27") (pin "2") (pinfunction "2_2") (pintype "passive"))
      (node (ref "U7") (pin "5") (pinfunction "A3_5") (pintype "passive"))
    )
    (net (code "112") (name "Net-(U7-A4)") (class "Default")
      (node (ref "R28") (pin "2") (pinfunction "2_2") (pintype "passive"))
      (node (ref "U7") (pin "7") (pinfunction "A4_7") (pintype "passive"))
    )
    (net (code "113") (name "Net-(U8-A1)") (class "Default")
      (node (ref "R33") (pin "2") (pinfunction "2_2") (pintype "passive"))
      (node (ref "U8") (pin "1") (pinfunction "A1_1") (pintype "passive"))
    )
    (net (code "114") (name "Net-(U8-A2)") (class "Default")
      (node (ref "R34") (pin "2") (pinfunction "2_2") (pintype "passive"))
      (node (ref "U8") (pin "3") (pinfunction "A2_3") (pintype "passive"))
    )
    (net (code "115") (name "Net-(U8-A3)") (class "Default")
      (node (ref "R35") (pin "2") (pinfunction "2_2") (pintype "passive"))
      (node (ref "U8") (pin "5") (pinfunction "A3_5") (pintype "passive"))
    )
    (net (code "116") (name "Net-(U8-A4)") (class "Default")
      (node (ref "R36") (pin "2") (pinfunction "2_2") (pintype "passive"))
      (node (ref "U8") (pin "7") (pinfunction "A4_7") (pintype "passive"))
    )
    (net (code "117") (name "Net-(U9-A1)") (class "Default")
      (node (ref "R41") (pin "2") (pinfunction "2_2") (pintype "passive"))
      (node (ref "U9") (pin "1") (pinfunction "A1_1") (pintype "passive"))
    )
    (net (code "118") (name "Net-(U9-A2)") (class "Default")
      (node (ref "R42") (pin "2") (pinfunction "2_2") (pintype "passive"))
      (node (ref "U9") (pin "3") (pinfunction "A2_3") (pintype "passive"))
    )
    (net (code "119") (name "Net-(U9-A3)") (class "Default")
      (node (ref "R43") (pin "2") (pinfunction "2_2") (pintype "passive"))
      (node (ref "U9") (pin "5") (pinfunction "A3_5") (pintype "passive"))
    )
    (net (code "120") (name "Net-(U9-A4)") (class "Default")
      (node (ref "R44") (pin "2") (pinfunction "2_2") (pintype "passive"))
      (node (ref "U9") (pin "7") (pinfunction "A4_7") (pintype "passive"))
    )
    (net (code "121") (name "Net-(U10-A1)") (class "Default")
      (node (ref "R49") (pin "2") (pinfunction "2_2") (pintype "passive"))
      (node (ref "U10") (pin "1") (pinfunction "A1_1") (pintype "passive"))
    )
    (net (code "122") (name "RXI") (class "Default")
      (node (ref "J1") (pin "2") (pinfunction "2_2") (pintype "passive"))
      (node (ref "J3") (pin "2") (pinfunction "RXI_2") (pintype "passive"))
    )
    (net (code "123") (name "TXO") (class "Default")
      (node (ref "J1") (pin "1") (pinfunction "1_1") (pintype "passive"))
      (node (ref "J3") (pin "3") (pinfunction "TXO_3") (pintype "passive"))
    )
    (net (code "124") (name "VCCA") (class "Default")
      (node (ref "J24") (pin "1") (pinfunction "1_1") (pintype "bidirectional"))
      (node (ref "J24") (pin "2") (pinfunction "2_2") (pintype "bidirectional"))
      (node (ref "J25") (pin "1") (pinfunction "1_1") (pintype "bidirectional"))
      (node (ref "J25") (pin "2") (pinfunction "2_2") (pintype "bidirectional"))
      (node (ref "J26") (pin "1") (pinfunction "1_1") (pintype "bidirectional"))
      (node (ref "J26") (pin "2") (pinfunction "2_2") (pintype "bidirectional"))
      (node (ref "J27") (pin "1") (pinfunction "1_1") (pintype "bidirectional"))
      (node (ref "J27") (pin "2") (pinfunction "2_2") (pintype "bidirectional"))
      (node (ref "J28") (pin "1") (pinfunction "1_1") (pintype "bidirectional"))
      (node (ref "J28") (pin "2") (pinfunction "2_2") (pintype "bidirectional"))
      (node (ref "J29") (pin "1") (pinfunction "1_1") (pintype "bidirectional"))
      (node (ref "J29") (pin "2") (pinfunction "2_2") (pintype "bidirectional"))
      (node (ref "J30") (pin "1") (pinfunction "1_1") (pintype "bidirectional"))
      (node (ref "J30") (pin "2") (pinfunction "2_2") (pintype "bidirectional"))
      (node (ref "J31") (pin "1") (pinfunction "1_1") (pintype "bidirectional"))
      (node (ref "J31") (pin "2") (pinfunction "2_2") (pintype "bidirectional"))
      (node (ref "J43") (pin "2") (pinfunction "2_2") (pintype "passive"))
      (node (ref "R63") (pin "1") (pinfunction "1_1") (pintype "passive"))
      (node (ref "R64") (pin "1") (pinfunction "1_1") (pintype "passive"))
      (node (ref "R65") (pin "1") (pinfunction "1_1") (pintype "passive"))
      (node (ref "R66") (pin "1") (pinfunction "1_1") (pintype "passive"))
      (node (ref "U1") (pin "10") (pinfunction "CO4_10") (pintype "passive"))
      (node (ref "U1") (pin "12") (pinfunction "CO3_12") (pintype "passive"))
      (node (ref "U1") (pin "14") (pinfunction "CO2_14") (pintype "passive"))
      (node (ref "U1") (pin "16") (pinfunction "CO1_16") (pintype "passive"))
      (node (ref "U4") (pin "24") (pinfunction "VDD_24") (pintype "power_in"))
      (node (ref "U5") (pin "10") (pinfunction "CO4_10") (pintype "passive"))
      (node (ref "U5") (pin "12") (pinfunction "CO3_12") (pintype "passive"))
      (node (ref "U5") (pin "14") (pinfunction "CO2_14") (pintype "passive"))
      (node (ref "U5") (pin "16") (pinfunction "CO1_16") (pintype "passive"))
      (node (ref "U6") (pin "10") (pinfunction "CO4_10") (pintype "passive"))
      (node (ref "U6") (pin "12") (pinfunction "CO3_12") (pintype "passive"))
      (node (ref "U6") (pin "14") (pinfunction "CO2_14") (pintype "passive"))
      (node (ref "U6") (pin "16") (pinfunction "CO1_16") (pintype "passive"))
      (node (ref "U9") (pin "10") (pinfunction "CO4_10") (pintype "passive"))
      (node (ref "U9") (pin "12") (pinfunction "CO3_12") (pintype "passive"))
      (node (ref "U9") (pin "14") (pinfunction "CO2_14") (pintype "passive"))
      (node (ref "U9") (pin "16") (pinfunction "CO1_16") (pintype "passive"))
    )
    (net (code "125") (name "VCCD") (class "Default")
      (node (ref "J45") (pin "1") (pinfunction "1_1") (pintype "bidirectional"))
      (node (ref "J45") (pin "2") (pinfunction "2_2") (pintype "bidirectional"))
      (node (ref "J46") (pin "1") (pinfunction "1_1") (pintype "bidirectional"))
      (node (ref "J46") (pin "2") (pinfunction "2_2") (pintype "bidirectional"))
      (node (ref "J47") (pin "1") (pinfunction "1_1") (pintype "bidirectional"))
      (node (ref "J47") (pin "2") (pinfunction "2_2") (pintype "bidirectional"))
      (node (ref "J48") (pin "1") (pinfunction "1_1") (pintype "bidirectional"))
      (node (ref "J48") (pin "2") (pinfunction "2_2") (pintype "bidirectional"))
      (node (ref "J53") (pin "2") (pinfunction "2_2") (pintype "passive"))
    )
    (net (code "126") (name "unconnected-(J3-CTS-Pad5)") (class "Default")
      (node (ref "J3") (pin "5") (pinfunction "CTS_5") (pintype "passive"))
    )
    (net (code "127") (name "unconnected-(J3-DTR-Pad1)") (class "Default")
      (node (ref "J3") (pin "1") (pinfunction "DTR_1") (pintype "passive"))
    )
    (net (code "128") (name "unconnected-(X1-4_4.3V_GREEN-Pad4)") (class "Default")
      (node (ref "X1") (pin "4") (pinfunction "4_4.3V_GREEN_4") (pintype "passive"))
    )
    (net (code "129") (name "unconnected-(X1-5_SCL_YELLOW-Pad5)") (class "Default")
      (node (ref "X1") (pin "5") (pinfunction "5_SCL_YELLOW_5") (pintype "passive"))
    )
    (net (code "130") (name "unconnected-(X1-6_SDA_BLUE-Pad6)") (class "Default")
      (node (ref "X1") (pin "6") (pinfunction "6_SDA_BLUE_6") (pintype "passive"))
    )
    (net (code "131") (name "unconnected-(X2-4_4.3V_GREEN-Pad4)") (class "Default")
      (node (ref "X2") (pin "4") (pinfunction "4_4.3V_GREEN_4") (pintype "passive"))
    )
    (net (code "132") (name "unconnected-(X2-5_SCL_YELLOW-Pad5)") (class "Default")
      (node (ref "X2") (pin "5") (pinfunction "5_SCL_YELLOW_5") (pintype "passive"))
    )
    (net (code "133") (name "unconnected-(X2-6_SDA_BLUE-Pad6)") (class "Default")
      (node (ref "X2") (pin "6") (pinfunction "6_SDA_BLUE_6") (pintype "passive"))
    )
    (net (code "134") (name "unconnected-(X3-4_4.3V_GREEN-Pad4)") (class "Default")
      (node (ref "X3") (pin "4") (pinfunction "4_4.3V_GREEN_4") (pintype "passive"))
    )
    (net (code "135") (name "unconnected-(X3-5_SCL_YELLOW-Pad5)") (class "Default")
      (node (ref "X3") (pin "5") (pinfunction "5_SCL_YELLOW_5") (pintype "passive"))
    )
    (net (code "136") (name "unconnected-(X3-6_SDA_BLUE-Pad6)") (class "Default")
      (node (ref "X3") (pin "6") (pinfunction "6_SDA_BLUE_6") (pintype "passive"))
    )
    (net (code "137") (name "unconnected-(X4-4_4.3V_GREEN-Pad4)") (class "Default")
      (node (ref "X4") (pin "4") (pinfunction "4_4.3V_GREEN_4") (pintype "passive"))
    )
    (net (code "138") (name "unconnected-(X4-5_SCL_YELLOW-Pad5)") (class "Default")
      (node (ref "X4") (pin "5") (pinfunction "5_SCL_YELLOW_5") (pintype "passive"))
    )
    (net (code "139") (name "unconnected-(X4-6_SDA_BLUE-Pad6)") (class "Default")
      (node (ref "X4") (pin "6") (pinfunction "6_SDA_BLUE_6") (pintype "passive"))
    )
  )
)
